# dashboard.net
KiCad netlist of a schematic drawn in EAGLE
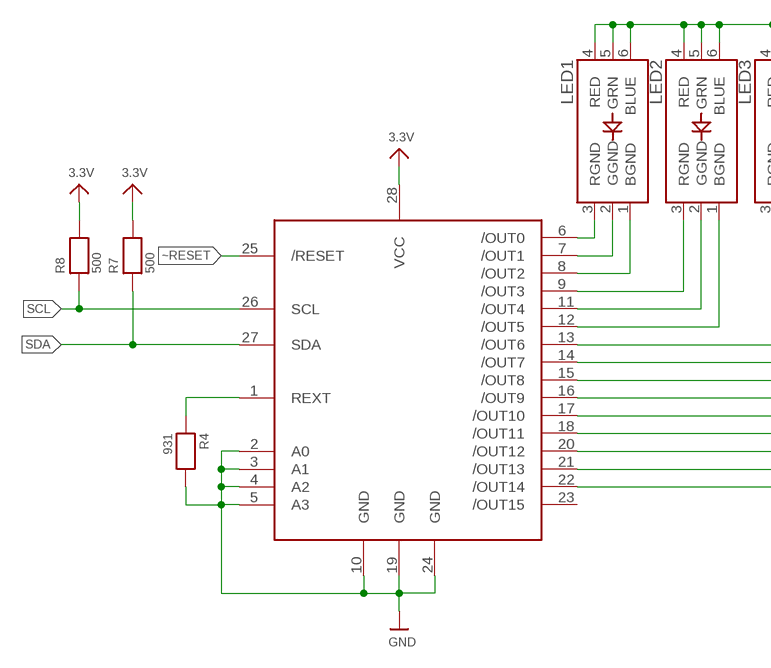
[diagram p0: schematic, sheet 1, part 1 of 2]
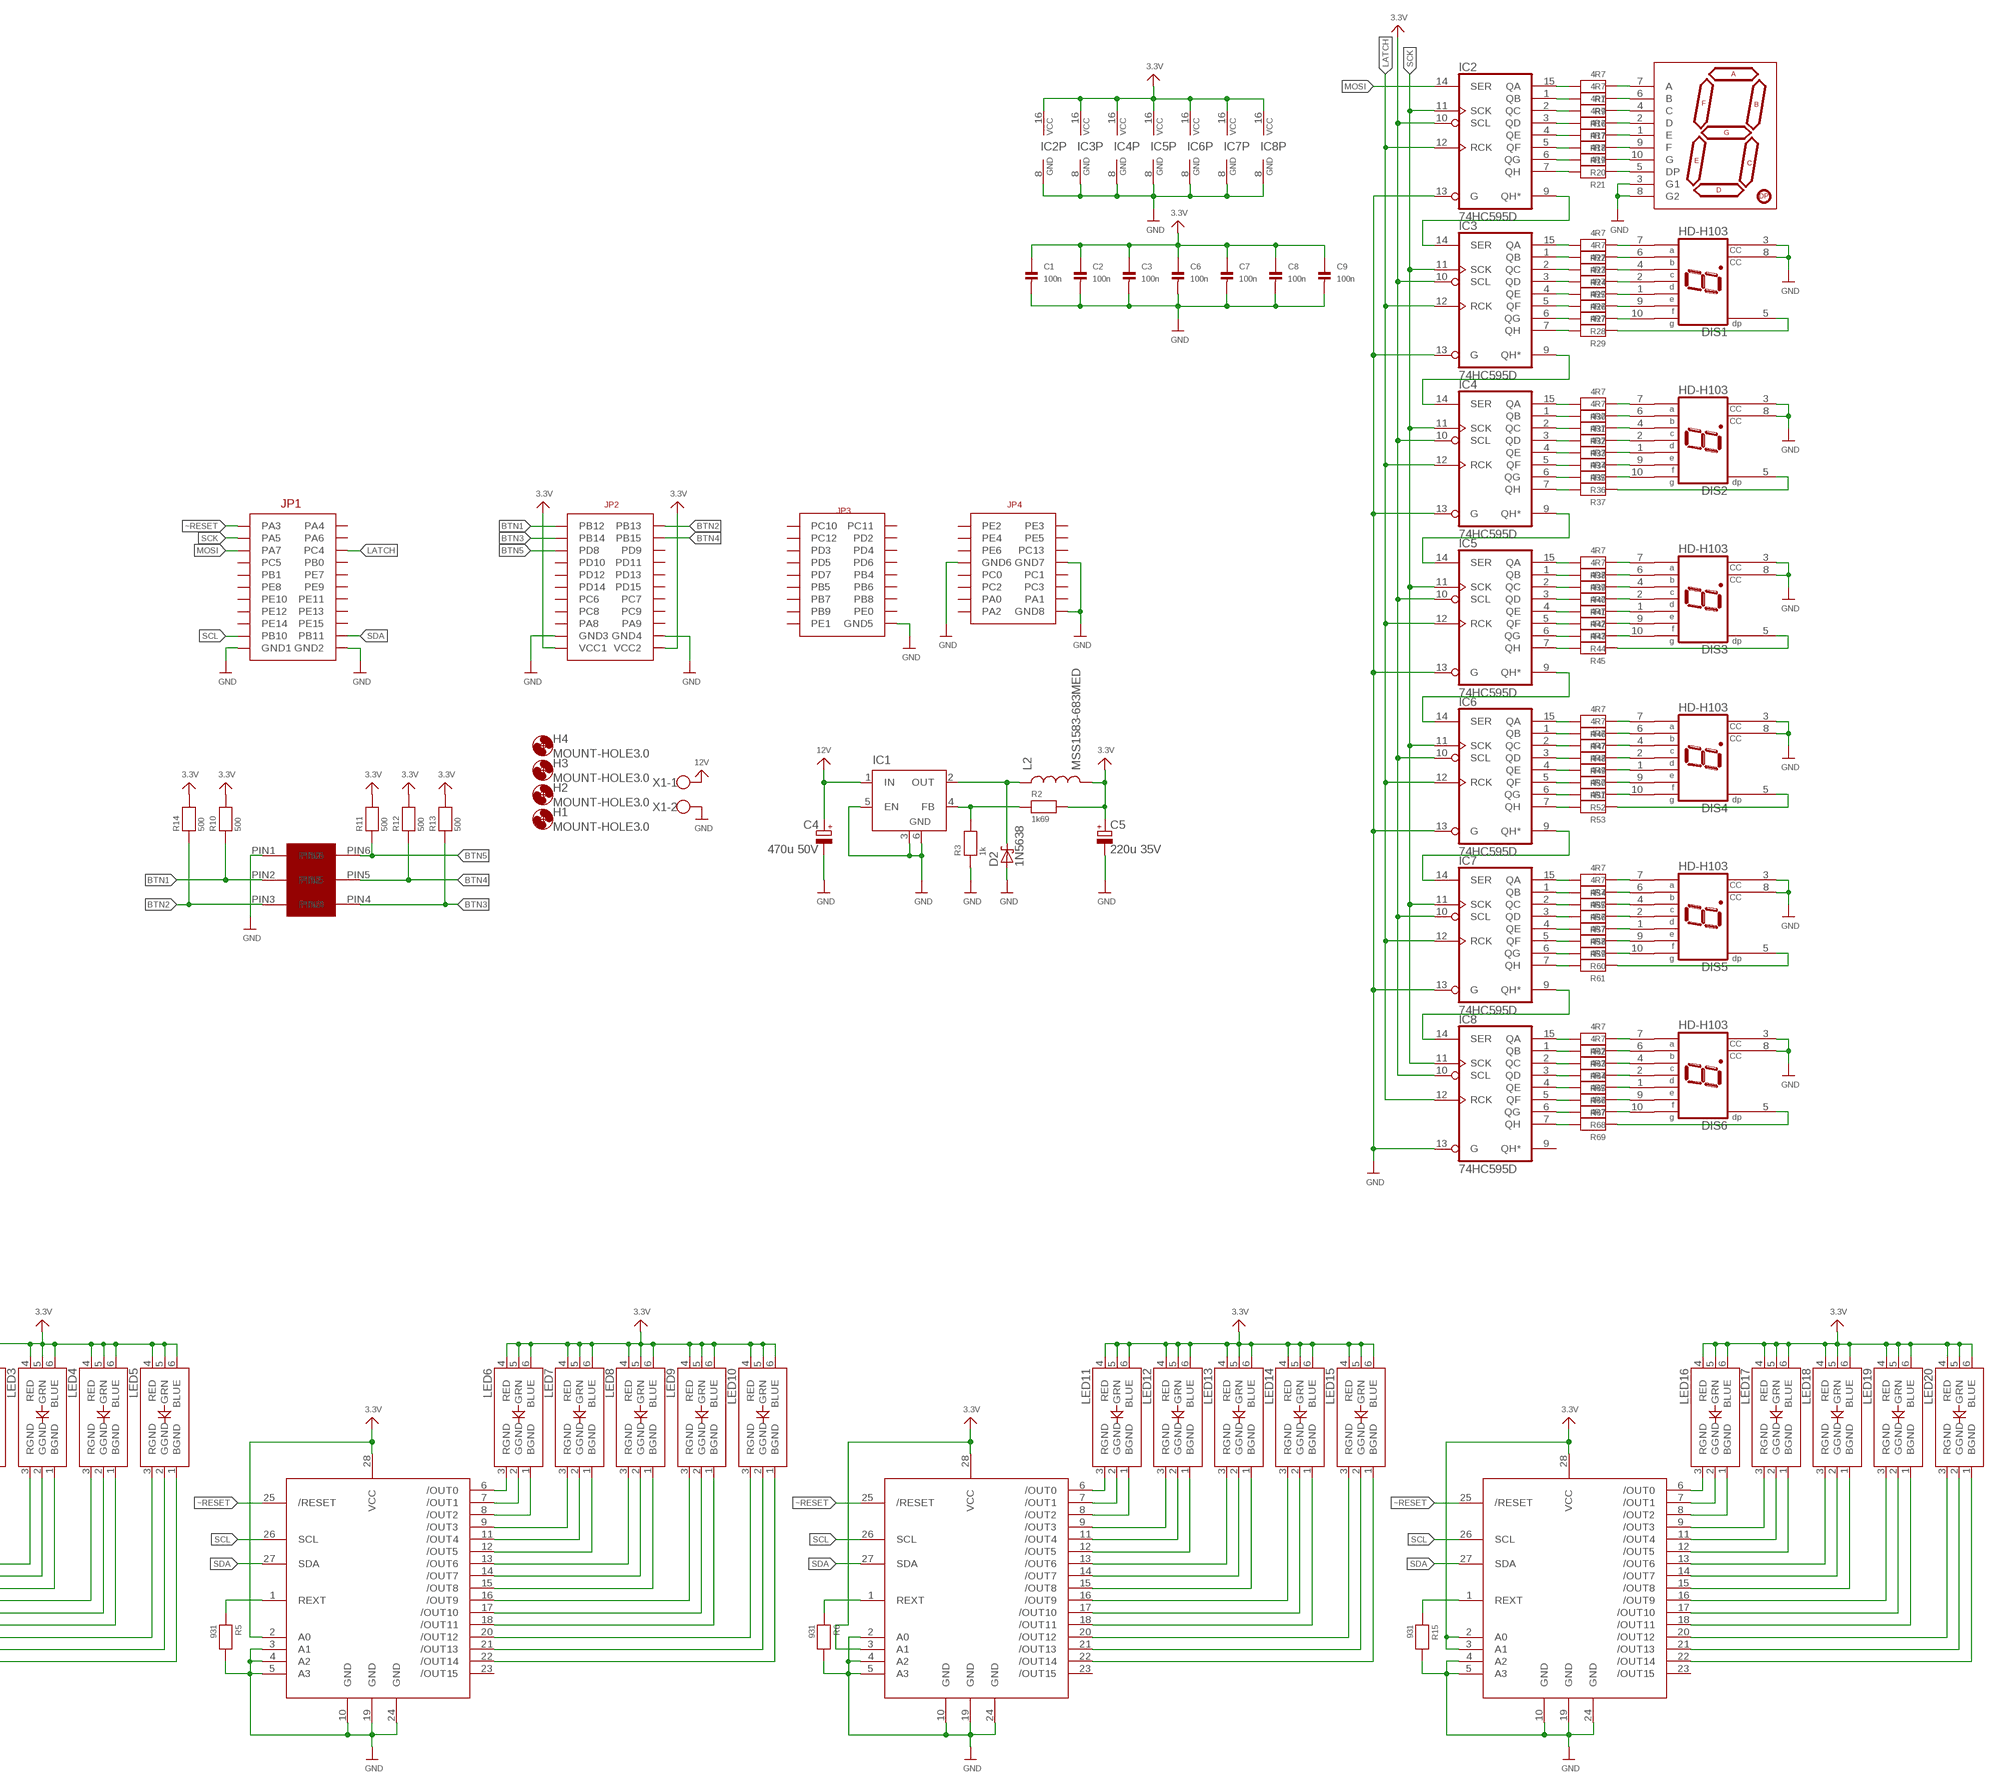
[diagram p1: schematic, sheet 1, part 2 of 2]

(export (version "E")
  (design (tool "Eeschema 10.0.6"))
  (components
    (comp (ref "C1")
      (value "100n")
      (footprint "eagle-import:_0603")
      (libsource (lib "eagle-import") (part "CAP_CERAMIC_0603"))
    )
    (comp (ref "C2")
      (value "100n")
      (footprint "eagle-import:_0603")
      (libsource (lib "eagle-import") (part "CAP_CERAMIC_0603"))
    )
    (comp (ref "C3")
      (value "100n")
      (footprint "eagle-import:_0603")
      (libsource (lib "eagle-import") (part "CAP_CERAMIC_0603"))
    )
    (comp (ref "C4")
      (value "470u 50V")
      (footprint "eagle-import:E5-13")
      (libsource (lib "eagle-import") (part "CPOL-EUE5-13"))
    )
    (comp (ref "C5")
      (value "220u 35V")
      (footprint "eagle-import:E3,5-8")
      (libsource (lib "eagle-import") (part "CPOL-EUE3.5-8"))
    )
    (comp (ref "C6")
      (value "100n")
      (footprint "eagle-import:_0603")
      (libsource (lib "eagle-import") (part "CAP_CERAMIC_0603"))
    )
    (comp (ref "C7")
      (value "100n")
      (footprint "eagle-import:_0603")
      (libsource (lib "eagle-import") (part "CAP_CERAMIC_0603"))
    )
    (comp (ref "C8")
      (value "100n")
      (footprint "eagle-import:_0603")
      (libsource (lib "eagle-import") (part "CAP_CERAMIC_0603"))
    )
    (comp (ref "C9")
      (value "100n")
      (footprint "eagle-import:_0603")
      (libsource (lib "eagle-import") (part "CAP_CERAMIC_0603"))
    )
    (comp (ref "D2")
      (value "1N5638")
      (footprint "eagle-import:DO13M")
      (libsource (lib "eagle-import") (part "1N5638"))
    )
    (comp (ref "DIS1")
      (value "HD-H103")
      (footprint "eagle-import:HDSP-M")
      (libsource (lib "eagle-import") (part "HD-H103"))
    )
    (comp (ref "DIS2")
      (value "HD-H103")
      (footprint "eagle-import:HDSP-M")
      (libsource (lib "eagle-import") (part "HD-H103"))
    )
    (comp (ref "DIS3")
      (value "HD-H103")
      (footprint "eagle-import:HDSP-M")
      (libsource (lib "eagle-import") (part "HD-H103"))
    )
    (comp (ref "DIS4")
      (value "HD-H103")
      (footprint "eagle-import:HDSP-M")
      (libsource (lib "eagle-import") (part "HD-H103"))
    )
    (comp (ref "DIS5")
      (value "HD-H103")
      (footprint "eagle-import:HDSP-M")
      (libsource (lib "eagle-import") (part "HD-H103"))
    )
    (comp (ref "DIS6")
      (value "HD-H103")
      (footprint "eagle-import:HDSP-M")
      (libsource (lib "eagle-import") (part "HD-H103"))
    )
    (comp (ref "H1")
      (value "MOUNT-HOLE3.0")
      (footprint "eagle-import:3,0")
      (libsource (lib "eagle-import") (part "MOUNT-HOLE3.0"))
    )
    (comp (ref "H2")
      (value "MOUNT-HOLE3.0")
      (footprint "eagle-import:3,0")
      (libsource (lib "eagle-import") (part "MOUNT-HOLE3.0"))
    )
    (comp (ref "H3")
      (value "MOUNT-HOLE3.0")
      (footprint "eagle-import:3,0")
      (libsource (lib "eagle-import") (part "MOUNT-HOLE3.0"))
    )
    (comp (ref "H4")
      (value "MOUNT-HOLE3.0")
      (footprint "eagle-import:3,0")
      (libsource (lib "eagle-import") (part "MOUNT-HOLE3.0"))
    )
    (comp (ref "IC1")
      (value "LM2596S")
      (footprint "eagle-import:TO263-5")
      (libsource (lib "eagle-import") (part "LM2596S"))
    )
    (comp (ref "IC2")
      (value "74HC595D")
      (footprint "eagle-import:SO16")
      (libsource (lib "eagle-import") (part "74595DHC"))
    )
    (comp (ref "IC3")
      (value "74HC595D")
      (footprint "eagle-import:SO16")
      (libsource (lib "eagle-import") (part "74595DHC"))
    )
    (comp (ref "IC4")
      (value "74HC595D")
      (footprint "eagle-import:SO16")
      (libsource (lib "eagle-import") (part "74595DHC"))
    )
    (comp (ref "IC5")
      (value "74HC595D")
      (footprint "eagle-import:SO16")
      (libsource (lib "eagle-import") (part "74595DHC"))
    )
    (comp (ref "IC6")
      (value "74HC595D")
      (footprint "eagle-import:SO16")
      (libsource (lib "eagle-import") (part "74595DHC"))
    )
    (comp (ref "IC7")
      (value "74HC595D")
      (footprint "eagle-import:SO16")
      (libsource (lib "eagle-import") (part "74595DHC"))
    )
    (comp (ref "IC8")
      (value "74HC595D")
      (footprint "eagle-import:SO16")
      (libsource (lib "eagle-import") (part "74595DHC"))
    )
    (comp (ref "L2")
      (value "MSS1583-683MED")
      (footprint "eagle-import:CDRH125")
      (libsource (lib "eagle-import") (part "INDUCTORPWR"))
    )
    (comp (ref "LED1")
      (value "LED_RGB_PLCC6CREE-CLV6A")
      (footprint "eagle-import:RGBLED_PLCC6")
      (libsource (lib "eagle-import") (part "LED_RGB_PLCC6CREE-CLV6A"))
    )
    (comp (ref "LED2")
      (value "LED_RGB_PLCC6CREE-CLV6A")
      (footprint "eagle-import:RGBLED_PLCC6")
      (libsource (lib "eagle-import") (part "LED_RGB_PLCC6CREE-CLV6A"))
    )
    (comp (ref "LED3")
      (value "LED_RGB_PLCC6CREE-CLV6A")
      (footprint "eagle-import:RGBLED_PLCC6")
      (libsource (lib "eagle-import") (part "LED_RGB_PLCC6CREE-CLV6A"))
    )
    (comp (ref "LED4")
      (value "LED_RGB_PLCC6CREE-CLV6A")
      (footprint "eagle-import:RGBLED_PLCC6")
      (libsource (lib "eagle-import") (part "LED_RGB_PLCC6CREE-CLV6A"))
    )
    (comp (ref "LED5")
      (value "LED_RGB_PLCC6CREE-CLV6A")
      (footprint "eagle-import:RGBLED_PLCC6")
      (libsource (lib "eagle-import") (part "LED_RGB_PLCC6CREE-CLV6A"))
    )
    (comp (ref "LED6")
      (value "LED_RGB_PLCC6CREE-CLV6A")
      (footprint "eagle-import:RGBLED_PLCC6")
      (libsource (lib "eagle-import") (part "LED_RGB_PLCC6CREE-CLV6A"))
    )
    (comp (ref "LED7")
      (value "LED_RGB_PLCC6CREE-CLV6A")
      (footprint "eagle-import:RGBLED_PLCC6")
      (libsource (lib "eagle-import") (part "LED_RGB_PLCC6CREE-CLV6A"))
    )
    (comp (ref "LED8")
      (value "LED_RGB_PLCC6CREE-CLV6A")
      (footprint "eagle-import:RGBLED_PLCC6")
      (libsource (lib "eagle-import") (part "LED_RGB_PLCC6CREE-CLV6A"))
    )
    (comp (ref "LED9")
      (value "LED_RGB_PLCC6CREE-CLV6A")
      (footprint "eagle-import:RGBLED_PLCC6")
      (libsource (lib "eagle-import") (part "LED_RGB_PLCC6CREE-CLV6A"))
    )
    (comp (ref "LED10")
      (value "LED_RGB_PLCC6CREE-CLV6A")
      (footprint "eagle-import:RGBLED_PLCC6")
      (libsource (lib "eagle-import") (part "LED_RGB_PLCC6CREE-CLV6A"))
    )
    (comp (ref "LED11")
      (value "LED_RGB_PLCC6CREE-CLV6A")
      (footprint "eagle-import:RGBLED_PLCC6")
      (libsource (lib "eagle-import") (part "LED_RGB_PLCC6CREE-CLV6A"))
    )
    (comp (ref "LED12")
      (value "LED_RGB_PLCC6CREE-CLV6A")
      (footprint "eagle-import:RGBLED_PLCC6")
      (libsource (lib "eagle-import") (part "LED_RGB_PLCC6CREE-CLV6A"))
    )
    (comp (ref "LED13")
      (value "LED_RGB_PLCC6CREE-CLV6A")
      (footprint "eagle-import:RGBLED_PLCC6")
      (libsource (lib "eagle-import") (part "LED_RGB_PLCC6CREE-CLV6A"))
    )
    (comp (ref "LED14")
      (value "LED_RGB_PLCC6CREE-CLV6A")
      (footprint "eagle-import:RGBLED_PLCC6")
      (libsource (lib "eagle-import") (part "LED_RGB_PLCC6CREE-CLV6A"))
    )
    (comp (ref "LED15")
      (value "LED_RGB_PLCC6CREE-CLV6A")
      (footprint "eagle-import:RGBLED_PLCC6")
      (libsource (lib "eagle-import") (part "LED_RGB_PLCC6CREE-CLV6A"))
    )
    (comp (ref "LED16")
      (value "LED_RGB_PLCC6CREE-CLV6A")
      (footprint "eagle-import:RGBLED_PLCC6")
      (libsource (lib "eagle-import") (part "LED_RGB_PLCC6CREE-CLV6A"))
    )
    (comp (ref "LED17")
      (value "LED_RGB_PLCC6CREE-CLV6A")
      (footprint "eagle-import:RGBLED_PLCC6")
      (libsource (lib "eagle-import") (part "LED_RGB_PLCC6CREE-CLV6A"))
    )
    (comp (ref "LED18")
      (value "LED_RGB_PLCC6CREE-CLV6A")
      (footprint "eagle-import:RGBLED_PLCC6")
      (libsource (lib "eagle-import") (part "LED_RGB_PLCC6CREE-CLV6A"))
    )
    (comp (ref "LED19")
      (value "LED_RGB_PLCC6CREE-CLV6A")
      (footprint "eagle-import:RGBLED_PLCC6")
      (libsource (lib "eagle-import") (part "LED_RGB_PLCC6CREE-CLV6A"))
    )
    (comp (ref "LED20")
      (value "LED_RGB_PLCC6CREE-CLV6A")
      (footprint "eagle-import:RGBLED_PLCC6")
      (libsource (lib "eagle-import") (part "LED_RGB_PLCC6CREE-CLV6A"))
    )
    (comp (ref "R1")
      (value "4R7")
      (footprint "eagle-import:_0603")
      (libsource (lib "eagle-import") (part "RESISTOR_0603"))
    )
    (comp (ref "R2")
      (value "1k69")
      (footprint "eagle-import:_0603")
      (libsource (lib "eagle-import") (part "RESISTOR_0603"))
    )
    (comp (ref "R3")
      (value "1k")
      (footprint "eagle-import:_0603")
      (libsource (lib "eagle-import") (part "RESISTOR_0603"))
    )
    (comp (ref "R4")
      (value "931")
      (footprint "eagle-import:_0603")
      (libsource (lib "eagle-import") (part "RESISTOR_0603"))
    )
    (comp (ref "R5")
      (value "931")
      (footprint "eagle-import:_0603")
      (libsource (lib "eagle-import") (part "RESISTOR_0603"))
    )
    (comp (ref "R6")
      (value "931")
      (footprint "eagle-import:_0603")
      (libsource (lib "eagle-import") (part "RESISTOR_0603"))
    )
    (comp (ref "R7")
      (value "500")
      (footprint "eagle-import:_0603")
      (libsource (lib "eagle-import") (part "RESISTOR_0603"))
    )
    (comp (ref "R8")
      (value "500")
      (footprint "eagle-import:_0603")
      (libsource (lib "eagle-import") (part "RESISTOR_0603"))
    )
    (comp (ref "R9")
      (value "4R7")
      (footprint "eagle-import:_0603")
      (libsource (lib "eagle-import") (part "RESISTOR_0603"))
    )
    (comp (ref "R10")
      (value "500")
      (footprint "eagle-import:_0805")
      (libsource (lib "eagle-import") (part "RESISTOR_0805"))
    )
    (comp (ref "R11")
      (value "500")
      (footprint "eagle-import:_0805")
      (libsource (lib "eagle-import") (part "RESISTOR_0805"))
    )
    (comp (ref "R12")
      (value "500")
      (footprint "eagle-import:_0805")
      (libsource (lib "eagle-import") (part "RESISTOR_0805"))
    )
    (comp (ref "R13")
      (value "500")
      (footprint "eagle-import:_0805")
      (libsource (lib "eagle-import") (part "RESISTOR_0805"))
    )
    (comp (ref "R14")
      (value "500")
      (footprint "eagle-import:_0805")
      (libsource (lib "eagle-import") (part "RESISTOR_0805"))
    )
    (comp (ref "R15")
      (value "931")
      (footprint "eagle-import:_0603")
      (libsource (lib "eagle-import") (part "RESISTOR_0603"))
    )
    (comp (ref "R16")
      (value "4R7")
      (footprint "eagle-import:_0603")
      (libsource (lib "eagle-import") (part "RESISTOR_0603"))
    )
    (comp (ref "R17")
      (value "4R7")
      (footprint "eagle-import:_0603")
      (libsource (lib "eagle-import") (part "RESISTOR_0603"))
    )
    (comp (ref "R18")
      (value "4R7")
      (footprint "eagle-import:_0603")
      (libsource (lib "eagle-import") (part "RESISTOR_0603"))
    )
    (comp (ref "R19")
      (value "4R7")
      (footprint "eagle-import:_0603")
      (libsource (lib "eagle-import") (part "RESISTOR_0603"))
    )
    (comp (ref "R20")
      (value "4R7")
      (footprint "eagle-import:_0603")
      (libsource (lib "eagle-import") (part "RESISTOR_0603"))
    )
    (comp (ref "R21")
      (value "4R7")
      (footprint "eagle-import:_0603")
      (libsource (lib "eagle-import") (part "RESISTOR_0603"))
    )
    (comp (ref "R22")
      (value "4R7")
      (footprint "eagle-import:_0603")
      (libsource (lib "eagle-import") (part "RESISTOR_0603"))
    )
    (comp (ref "R23")
      (value "4R7")
      (footprint "eagle-import:_0603")
      (libsource (lib "eagle-import") (part "RESISTOR_0603"))
    )
    (comp (ref "R24")
      (value "4R7")
      (footprint "eagle-import:_0603")
      (libsource (lib "eagle-import") (part "RESISTOR_0603"))
    )
    (comp (ref "R25")
      (value "4R7")
      (footprint "eagle-import:_0603")
      (libsource (lib "eagle-import") (part "RESISTOR_0603"))
    )
    (comp (ref "R26")
      (value "4R7")
      (footprint "eagle-import:_0603")
      (libsource (lib "eagle-import") (part "RESISTOR_0603"))
    )
    (comp (ref "R27")
      (value "4R7")
      (footprint "eagle-import:_0603")
      (libsource (lib "eagle-import") (part "RESISTOR_0603"))
    )
    (comp (ref "R28")
      (value "4R7")
      (footprint "eagle-import:_0603")
      (libsource (lib "eagle-import") (part "RESISTOR_0603"))
    )
    (comp (ref "R29")
      (value "4R7")
      (footprint "eagle-import:_0603")
      (libsource (lib "eagle-import") (part "RESISTOR_0603"))
    )
    (comp (ref "R30")
      (value "4R7")
      (footprint "eagle-import:_0603")
      (libsource (lib "eagle-import") (part "RESISTOR_0603"))
    )
    (comp (ref "R31")
      (value "4R7")
      (footprint "eagle-import:_0603")
      (libsource (lib "eagle-import") (part "RESISTOR_0603"))
    )
    (comp (ref "R32")
      (value "4R7")
      (footprint "eagle-import:_0603")
      (libsource (lib "eagle-import") (part "RESISTOR_0603"))
    )
    (comp (ref "R33")
      (value "4R7")
      (footprint "eagle-import:_0603")
      (libsource (lib "eagle-import") (part "RESISTOR_0603"))
    )
    (comp (ref "R34")
      (value "4R7")
      (footprint "eagle-import:_0603")
      (libsource (lib "eagle-import") (part "RESISTOR_0603"))
    )
    (comp (ref "R35")
      (value "4R7")
      (footprint "eagle-import:_0603")
      (libsource (lib "eagle-import") (part "RESISTOR_0603"))
    )
    (comp (ref "R36")
      (value "4R7")
      (footprint "eagle-import:_0603")
      (libsource (lib "eagle-import") (part "RESISTOR_0603"))
    )
    (comp (ref "R37")
      (value "4R7")
      (footprint "eagle-import:_0603")
      (libsource (lib "eagle-import") (part "RESISTOR_0603"))
    )
    (comp (ref "R38")
      (value "4R7")
      (footprint "eagle-import:_0603")
      (libsource (lib "eagle-import") (part "RESISTOR_0603"))
    )
    (comp (ref "R39")
      (value "4R7")
      (footprint "eagle-import:_0603")
      (libsource (lib "eagle-import") (part "RESISTOR_0603"))
    )
    (comp (ref "R40")
      (value "4R7")
      (footprint "eagle-import:_0603")
      (libsource (lib "eagle-import") (part "RESISTOR_0603"))
    )
    (comp (ref "R41")
      (value "4R7")
      (footprint "eagle-import:_0603")
      (libsource (lib "eagle-import") (part "RESISTOR_0603"))
    )
    (comp (ref "R42")
      (value "4R7")
      (footprint "eagle-import:_0603")
      (libsource (lib "eagle-import") (part "RESISTOR_0603"))
    )
    (comp (ref "R43")
      (value "4R7")
      (footprint "eagle-import:_0603")
      (libsource (lib "eagle-import") (part "RESISTOR_0603"))
    )
    (comp (ref "R44")
      (value "4R7")
      (footprint "eagle-import:_0603")
      (libsource (lib "eagle-import") (part "RESISTOR_0603"))
    )
    (comp (ref "R45")
      (value "4R7")
      (footprint "eagle-import:_0603")
      (libsource (lib "eagle-import") (part "RESISTOR_0603"))
    )
    (comp (ref "R46")
      (value "4R7")
      (footprint "eagle-import:_0603")
      (libsource (lib "eagle-import") (part "RESISTOR_0603"))
    )
    (comp (ref "R47")
      (value "4R7")
      (footprint "eagle-import:_0603")
      (libsource (lib "eagle-import") (part "RESISTOR_0603"))
    )
    (comp (ref "R48")
      (value "4R7")
      (footprint "eagle-import:_0603")
      (libsource (lib "eagle-import") (part "RESISTOR_0603"))
    )
    (comp (ref "R49")
      (value "4R7")
      (footprint "eagle-import:_0603")
      (libsource (lib "eagle-import") (part "RESISTOR_0603"))
    )
    (comp (ref "R50")
      (value "4R7")
      (footprint "eagle-import:_0603")
      (libsource (lib "eagle-import") (part "RESISTOR_0603"))
    )
    (comp (ref "R51")
      (value "4R7")
      (footprint "eagle-import:_0603")
      (libsource (lib "eagle-import") (part "RESISTOR_0603"))
    )
    (comp (ref "R52")
      (value "4R7")
      (footprint "eagle-import:_0603")
      (libsource (lib "eagle-import") (part "RESISTOR_0603"))
    )
    (comp (ref "R53")
      (value "4R7")
      (footprint "eagle-import:_0603")
      (libsource (lib "eagle-import") (part "RESISTOR_0603"))
    )
    (comp (ref "R54")
      (value "4R7")
      (footprint "eagle-import:_0603")
      (libsource (lib "eagle-import") (part "RESISTOR_0603"))
    )
    (comp (ref "R55")
      (value "4R7")
      (footprint "eagle-import:_0603")
      (libsource (lib "eagle-import") (part "RESISTOR_0603"))
    )
    (comp (ref "R56")
      (value "4R7")
      (footprint "eagle-import:_0603")
      (libsource (lib "eagle-import") (part "RESISTOR_0603"))
    )
    (comp (ref "R57")
      (value "4R7")
      (footprint "eagle-import:_0603")
      (libsource (lib "eagle-import") (part "RESISTOR_0603"))
    )
    (comp (ref "R58")
      (value "4R7")
      (footprint "eagle-import:_0603")
      (libsource (lib "eagle-import") (part "RESISTOR_0603"))
    )
    (comp (ref "R59")
      (value "4R7")
      (footprint "eagle-import:_0603")
      (libsource (lib "eagle-import") (part "RESISTOR_0603"))
    )
    (comp (ref "R60")
      (value "4R7")
      (footprint "eagle-import:_0603")
      (libsource (lib "eagle-import") (part "RESISTOR_0603"))
    )
    (comp (ref "R61")
      (value "4R7")
      (footprint "eagle-import:_0603")
      (libsource (lib "eagle-import") (part "RESISTOR_0603"))
    )
    (comp (ref "R62")
      (value "4R7")
      (footprint "eagle-import:_0603")
      (libsource (lib "eagle-import") (part "RESISTOR_0603"))
    )
    (comp (ref "R63")
      (value "4R7")
      (footprint "eagle-import:_0603")
      (libsource (lib "eagle-import") (part "RESISTOR_0603"))
    )
    (comp (ref "R64")
      (value "4R7")
      (footprint "eagle-import:_0603")
      (libsource (lib "eagle-import") (part "RESISTOR_0603"))
    )
    (comp (ref "R65")
      (value "4R7")
      (footprint "eagle-import:_0603")
      (libsource (lib "eagle-import") (part "RESISTOR_0603"))
    )
    (comp (ref "R66")
      (value "4R7")
      (footprint "eagle-import:_0603")
      (libsource (lib "eagle-import") (part "RESISTOR_0603"))
    )
    (comp (ref "R67")
      (value "4R7")
      (footprint "eagle-import:_0603")
      (libsource (lib "eagle-import") (part "RESISTOR_0603"))
    )
    (comp (ref "R68")
      (value "4R7")
      (footprint "eagle-import:_0603")
      (libsource (lib "eagle-import") (part "RESISTOR_0603"))
    )
    (comp (ref "R69")
      (value "4R7")
      (footprint "eagle-import:_0603")
      (libsource (lib "eagle-import") (part "RESISTOR_0603"))
    )
    (comp (ref "U$1")
      (value "CPU-BOARD")
      (footprint "eagle-import:CPU-BOARD-JP1")
      (libsource (lib "eagle-import") (part "CPU-BOARD"))
    )
    (comp (ref "U$9")
      (value "7-SEGMENT-DISPLAY-1\"-RED")
      (footprint "eagle-import:7-SEGMENT-1_PTH")
      (libsource (lib "eagle-import") (part "7-SEGMENT-DISPLAY-1{dblquote}-RED"))
    )
    (comp (ref "U$30")
      (value "TLC59116")
      (footprint "eagle-import:TSSOP28")
      (libsource (lib "eagle-import") (part "TLC59116"))
    )
    (comp (ref "U$33")
      (value "TLC59116")
      (footprint "eagle-import:TSSOP28")
      (libsource (lib "eagle-import") (part "TLC59116"))
    )
    (comp (ref "U$36")
      (value "TLC59116")
      (footprint "eagle-import:TSSOP28")
      (libsource (lib "eagle-import") (part "TLC59116"))
    )
    (comp (ref "U$42")
      (value "MICROFIT6")
      (footprint "eagle-import:MICROFIT6SOCK")
      (libsource (lib "eagle-import") (part "MICROFIT6"))
    )
    (comp (ref "U$51")
      (value "TLC59116")
      (footprint "eagle-import:TSSOP28")
      (libsource (lib "eagle-import") (part "TLC59116"))
    )
    (comp (ref "X1")
      (value "W237-102")
      (footprint "eagle-import:W237-102")
      (fields (field (name "MPN") "237-102"))
      (libsource (lib "eagle-import") (part "W237-102"))
    )
  )
  (nets
    (net (code "1") (name "/~{RESET}") (class "Default")
      (node (ref "U$1") (pin "P$1") (pinfunction "PA3_P$1") (pintype "bidirectional"))
      (node (ref "U$30") (pin "25") (pinfunction "/RESET_25") (pintype "bidirectional"))
      (node (ref "U$33") (pin "25") (pinfunction "/RESET_25") (pintype "bidirectional"))
      (node (ref "U$36") (pin "25") (pinfunction "/RESET_25") (pintype "bidirectional"))
      (node (ref "U$51") (pin "25") (pinfunction "/RESET_25") (pintype "bidirectional"))
    )
    (net (code "2") (name "3.3V") (class "Default")
      (node (ref "C1") (pin "1") (pinfunction "P$1_1") (pintype "passive"))
      (node (ref "C2") (pin "1") (pinfunction "P$1_1") (pintype "passive"))
      (node (ref "C3") (pin "1") (pinfunction "P$1_1") (pintype "passive"))
      (node (ref "C5") (pin "+") (pinfunction "+_+") (pintype "passive"))
      (node (ref "C6") (pin "1") (pinfunction "P$1_1") (pintype "passive"))
      (node (ref "C7") (pin "1") (pinfunction "P$1_1") (pintype "passive"))
      (node (ref "C8") (pin "1") (pinfunction "P$1_1") (pintype "passive"))
      (node (ref "C9") (pin "1") (pinfunction "P$1_1") (pintype "passive"))
      (node (ref "IC2") (pin "10") (pinfunction "SCL_10") (pintype "input"))
      (node (ref "IC2") (pin "16") (pinfunction "VCC_16") (pintype "power_in"))
      (node (ref "IC3") (pin "10") (pinfunction "SCL_10") (pintype "input"))
      (node (ref "IC3") (pin "16") (pinfunction "VCC_16") (pintype "power_in"))
      (node (ref "IC4") (pin "10") (pinfunction "SCL_10") (pintype "input"))
      (node (ref "IC4") (pin "16") (pinfunction "VCC_16") (pintype "power_in"))
      (node (ref "IC5") (pin "10") (pinfunction "SCL_10") (pintype "input"))
      (node (ref "IC5") (pin "16") (pinfunction "VCC_16") (pintype "power_in"))
      (node (ref "IC6") (pin "10") (pinfunction "SCL_10") (pintype "input"))
      (node (ref "IC6") (pin "16") (pinfunction "VCC_16") (pintype "power_in"))
      (node (ref "IC7") (pin "10") (pinfunction "SCL_10") (pintype "input"))
      (node (ref "IC7") (pin "16") (pinfunction "VCC_16") (pintype "power_in"))
      (node (ref "IC8") (pin "10") (pinfunction "SCL_10") (pintype "input"))
      (node (ref "IC8") (pin "16") (pinfunction "VCC_16") (pintype "power_in"))
      (node (ref "L2") (pin "2") (pinfunction "2_2") (pintype "passive"))
      (node (ref "LED1") (pin "4") (pinfunction "RED_4") (pintype "bidirectional"))
      (node (ref "LED1") (pin "5") (pinfunction "GRN_5") (pintype "bidirectional"))
      (node (ref "LED1") (pin "6") (pinfunction "BLUE_6") (pintype "bidirectional"))
      (node (ref "LED10") (pin "4") (pinfunction "RED_4") (pintype "bidirectional"))
      (node (ref "LED10") (pin "5") (pinfunction "GRN_5") (pintype "bidirectional"))
      (node (ref "LED10") (pin "6") (pinfunction "BLUE_6") (pintype "bidirectional"))
      (node (ref "LED11") (pin "4") (pinfunction "RED_4") (pintype "bidirectional"))
      (node (ref "LED11") (pin "5") (pinfunction "GRN_5") (pintype "bidirectional"))
      (node (ref "LED11") (pin "6") (pinfunction "BLUE_6") (pintype "bidirectional"))
      (node (ref "LED12") (pin "4") (pinfunction "RED_4") (pintype "bidirectional"))
      (node (ref "LED12") (pin "5") (pinfunction "GRN_5") (pintype "bidirectional"))
      (node (ref "LED12") (pin "6") (pinfunction "BLUE_6") (pintype "bidirectional"))
      (node (ref "LED13") (pin "4") (pinfunction "RED_4") (pintype "bidirectional"))
      (node (ref "LED13") (pin "5") (pinfunction "GRN_5") (pintype "bidirectional"))
      (node (ref "LED13") (pin "6") (pinfunction "BLUE_6") (pintype "bidirectional"))
      (node (ref "LED14") (pin "4") (pinfunction "RED_4") (pintype "bidirectional"))
      (node (ref "LED14") (pin "5") (pinfunction "GRN_5") (pintype "bidirectional"))
      (node (ref "LED14") (pin "6") (pinfunction "BLUE_6") (pintype "bidirectional"))
      (node (ref "LED15") (pin "4") (pinfunction "RED_4") (pintype "bidirectional"))
      (node (ref "LED15") (pin "5") (pinfunction "GRN_5") (pintype "bidirectional"))
      (node (ref "LED15") (pin "6") (pinfunction "BLUE_6") (pintype "bidirectional"))
      (node (ref "LED16") (pin "4") (pinfunction "RED_4") (pintype "bidirectional"))
      (node (ref "LED16") (pin "5") (pinfunction "GRN_5") (pintype "bidirectional"))
      (node (ref "LED16") (pin "6") (pinfunction "BLUE_6") (pintype "bidirectional"))
      (node (ref "LED17") (pin "4") (pinfunction "RED_4") (pintype "bidirectional"))
      (node (ref "LED17") (pin "5") (pinfunction "GRN_5") (pintype "bidirectional"))
      (node (ref "LED17") (pin "6") (pinfunction "BLUE_6") (pintype "bidirectional"))
      (node (ref "LED18") (pin "4") (pinfunction "RED_4") (pintype "bidirectional"))
      (node (ref "LED18") (pin "5") (pinfunction "GRN_5") (pintype "bidirectional"))
      (node (ref "LED18") (pin "6") (pinfunction "BLUE_6") (pintype "bidirectional"))
      (node (ref "LED19") (pin "4") (pinfunction "RED_4") (pintype "bidirectional"))
      (node (ref "LED19") (pin "5") (pinfunction "GRN_5") (pintype "bidirectional"))
      (node (ref "LED19") (pin "6") (pinfunction "BLUE_6") (pintype "bidirectional"))
      (node (ref "LED2") (pin "4") (pinfunction "RED_4") (pintype "bidirectional"))
      (node (ref "LED2") (pin "5") (pinfunction "GRN_5") (pintype "bidirectional"))
      (node (ref "LED2") (pin "6") (pinfunction "BLUE_6") (pintype "bidirectional"))
      (node (ref "LED20") (pin "4") (pinfunction "RED_4") (pintype "bidirectional"))
      (node (ref "LED20") (pin "5") (pinfunction "GRN_5") (pintype "bidirectional"))
      (node (ref "LED20") (pin "6") (pinfunction "BLUE_6") (pintype "bidirectional"))
      (node (ref "LED3") (pin "4") (pinfunction "RED_4") (pintype "bidirectional"))
      (node (ref "LED3") (pin "5") (pinfunction "GRN_5") (pintype "bidirectional"))
      (node (ref "LED3") (pin "6") (pinfunction "BLUE_6") (pintype "bidirectional"))
      (node (ref "LED4") (pin "4") (pinfunction "RED_4") (pintype "bidirectional"))
      (node (ref "LED4") (pin "5") (pinfunction "GRN_5") (pintype "bidirectional"))
      (node (ref "LED4") (pin "6") (pinfunction "BLUE_6") (pintype "bidirectional"))
      (node (ref "LED5") (pin "4") (pinfunction "RED_4") (pintype "bidirectional"))
      (node (ref "LED5") (pin "5") (pinfunction "GRN_5") (pintype "bidirectional"))
      (node (ref "LED5") (pin "6") (pinfunction "BLUE_6") (pintype "bidirectional"))
      (node (ref "LED6") (pin "4") (pinfunction "RED_4") (pintype "bidirectional"))
      (node (ref "LED6") (pin "5") (pinfunction "GRN_5") (pintype "bidirectional"))
      (node (ref "LED6") (pin "6") (pinfunction "BLUE_6") (pintype "bidirectional"))
      (node (ref "LED7") (pin "4") (pinfunction "RED_4") (pintype "bidirectional"))
      (node (ref "LED7") (pin "5") (pinfunction "GRN_5") (pintype "bidirectional"))
      (node (ref "LED7") (pin "6") (pinfunction "BLUE_6") (pintype "bidirectional"))
      (node (ref "LED8") (pin "4") (pinfunction "RED_4") (pintype "bidirectional"))
      (node (ref "LED8") (pin "5") (pinfunction "GRN_5") (pintype "bidirectional"))
      (node (ref "LED8") (pin "6") (pinfunction "BLUE_6") (pintype "bidirectional"))
      (node (ref "LED9") (pin "4") (pinfunction "RED_4") (pintype "bidirectional"))
      (node (ref "LED9") (pin "5") (pinfunction "GRN_5") (pintype "bidirectional"))
      (node (ref "LED9") (pin "6") (pinfunction "BLUE_6") (pintype "bidirectional"))
      (node (ref "R10") (pin "2") (pinfunction "2_2") (pintype "passive"))
      (node (ref "R11") (pin "2") (pinfunction "2_2") (pintype "passive"))
      (node (ref "R12") (pin "2") (pinfunction "2_2") (pintype "passive"))
      (node (ref "R13") (pin "2") (pinfunction "2_2") (pintype "passive"))
      (node (ref "R14") (pin "2") (pinfunction "2_2") (pintype "passive"))
      (node (ref "R2") (pin "2") (pinfunction "2_2") (pintype "passive"))
      (node (ref "R7") (pin "2") (pinfunction "2_2") (pintype "passive"))
      (node (ref "R8") (pin "2") (pinfunction "2_2") (pintype "passive"))
      (node (ref "U$1") (pin "P$43") (pinfunction "VCC1_P$43") (pintype "bidirectional"))
      (node (ref "U$1") (pin "P$44") (pinfunction "VCC2_P$44") (pintype "bidirectional"))
      (node (ref "U$30") (pin "28") (pinfunction "VCC_28") (pintype "bidirectional"))
      (node (ref "U$33") (pin "2") (pinfunction "A0_2") (pintype "bidirectional"))
      (node (ref "U$33") (pin "28") (pinfunction "VCC_28") (pintype "bidirectional"))
      (node (ref "U$36") (pin "28") (pinfunction "VCC_28") (pintype "bidirectional"))
      (node (ref "U$36") (pin "3") (pinfunction "A1_3") (pintype "bidirectional"))
      (node (ref "U$51") (pin "2") (pinfunction "A0_2") (pintype "bidirectional"))
      (node (ref "U$51") (pin "28") (pinfunction "VCC_28") (pintype "bidirectional"))
      (node (ref "U$51") (pin "3") (pinfunction "A1_3") (pintype "bidirectional"))
    )
    (net (code "3") (name "12V") (class "Default")
      (node (ref "C4") (pin "+") (pinfunction "+_+") (pintype "passive"))
      (node (ref "IC1") (pin "1") (pinfunction "IN_1") (pintype "input"))
      (node (ref "X1") (pin "1") (pinfunction "KL_1") (pintype "passive"))
    )
    (net (code "4") (name "BTN1") (class "Default")
      (node (ref "R10") (pin "1") (pinfunction "1_1") (pintype "passive"))
      (node (ref "U$1") (pin "P$23") (pinfunction "PB12_P$23") (pintype "bidirectional"))
      (node (ref "U$42") (pin "PIN2") (pinfunction "PIN2_PIN2") (pintype "bidirectional"))
    )
    (net (code "5") (name "BTN2") (class "Default")
      (node (ref "R14") (pin "1") (pinfunction "1_1") (pintype "passive"))
      (node (ref "U$1") (pin "P$24") (pinfunction "PB13_P$24") (pintype "bidirectional"))
      (node (ref "U$42") (pin "PIN3") (pinfunction "PIN3_PIN3") (pintype "bidirectional"))
    )
    (net (code "6") (name "BTN3") (class "Default")
      (node (ref "R13") (pin "1") (pinfunction "1_1") (pintype "passive"))
      (node (ref "U$1") (pin "P$25") (pinfunction "PB14_P$25") (pintype "bidirectional"))
      (node (ref "U$42") (pin "PIN4") (pinfunction "PIN4_PIN4") (pintype "bidirectional"))
    )
    (net (code "7") (name "BTN4") (class "Default")
      (node (ref "R12") (pin "1") (pinfunction "1_1") (pintype "passive"))
      (node (ref "U$1") (pin "P$26") (pinfunction "PB15_P$26") (pintype "bidirectional"))
      (node (ref "U$42") (pin "PIN5") (pinfunction "PIN5_PIN5") (pintype "bidirectional"))
    )
    (net (code "8") (name "BTN5") (class "Default")
      (node (ref "R11") (pin "1") (pinfunction "1_1") (pintype "passive"))
      (node (ref "U$1") (pin "P$27") (pinfunction "PD8_P$27") (pintype "bidirectional"))
      (node (ref "U$42") (pin "PIN6") (pinfunction "PIN6_PIN6") (pintype "bidirectional"))
    )
    (net (code "9") (name "GND") (class "Default")
      (node (ref "C1") (pin "2") (pinfunction "P$2_2") (pintype "passive"))
      (node (ref "C2") (pin "2") (pinfunction "P$2_2") (pintype "passive"))
      (node (ref "C3") (pin "2") (pinfunction "P$2_2") (pintype "passive"))
      (node (ref "C4") (pin "-") (pinfunction "-_-") (pintype "passive"))
      (node (ref "C5") (pin "-") (pinfunction "-_-") (pintype "passive"))
      (node (ref "C6") (pin "2") (pinfunction "P$2_2") (pintype "passive"))
      (node (ref "C7") (pin "2") (pinfunction "P$2_2") (pintype "passive"))
      (node (ref "C8") (pin "2") (pinfunction "P$2_2") (pintype "passive"))
      (node (ref "C9") (pin "2") (pinfunction "P$2_2") (pintype "passive"))
      (node (ref "D2") (pin "A") (pinfunction "A_A") (pintype "passive"))
      (node (ref "DIS1") (pin "3") (pinfunction "CC_3") (pintype "passive"))
      (node (ref "DIS1") (pin "8") (pinfunction "CC_8") (pintype "passive"))
      (node (ref "DIS2") (pin "3") (pinfunction "CC_3") (pintype "passive"))
      (node (ref "DIS2") (pin "8") (pinfunction "CC_8") (pintype "passive"))
      (node (ref "DIS3") (pin "3") (pinfunction "CC_3") (pintype "passive"))
      (node (ref "DIS3") (pin "8") (pinfunction "CC_8") (pintype "passive"))
      (node (ref "DIS4") (pin "3") (pinfunction "CC_3") (pintype "passive"))
      (node (ref "DIS4") (pin "8") (pinfunction "CC_8") (pintype "passive"))
      (node (ref "DIS5") (pin "3") (pinfunction "CC_3") (pintype "passive"))
      (node (ref "DIS5") (pin "8") (pinfunction "CC_8") (pintype "passive"))
      (node (ref "DIS6") (pin "3") (pinfunction "CC_3") (pintype "passive"))
      (node (ref "DIS6") (pin "8") (pinfunction "CC_8") (pintype "passive"))
      (node (ref "IC1") (pin "3") (pinfunction "GND_3") (pintype "power_in"))
      (node (ref "IC1") (pin "5") (pinfunction "EN_5") (pintype "input"))
      (node (ref "IC1") (pin "6") (pinfunction "GND_6") (pintype "power_in"))
      (node (ref "IC2") (pin "13") (pinfunction "G_13") (pintype "input"))
      (node (ref "IC2") (pin "8") (pinfunction "GND_8") (pintype "power_in"))
      (node (ref "IC3") (pin "13") (pinfunction "G_13") (pintype "input"))
      (node (ref "IC3") (pin "8") (pinfunction "GND_8") (pintype "power_in"))
      (node (ref "IC4") (pin "13") (pinfunction "G_13") (pintype "input"))
      (node (ref "IC4") (pin "8") (pinfunction "GND_8") (pintype "power_in"))
      (node (ref "IC5") (pin "13") (pinfunction "G_13") (pintype "input"))
      (node (ref "IC5") (pin "8") (pinfunction "GND_8") (pintype "power_in"))
      (node (ref "IC6") (pin "13") (pinfunction "G_13") (pintype "input"))
      (node (ref "IC6") (pin "8") (pinfunction "GND_8") (pintype "power_in"))
      (node (ref "IC7") (pin "13") (pinfunction "G_13") (pintype "input"))
      (node (ref "IC7") (pin "8") (pinfunction "GND_8") (pintype "power_in"))
      (node (ref "IC8") (pin "13") (pinfunction "G_13") (pintype "input"))
      (node (ref "IC8") (pin "8") (pinfunction "GND_8") (pintype "power_in"))
      (node (ref "R15") (pin "2") (pinfunction "2_2") (pintype "passive"))
      (node (ref "R3") (pin "1") (pinfunction "1_1") (pintype "passive"))
      (node (ref "R4") (pin "2") (pinfunction "2_2") (pintype "passive"))
      (node (ref "R5") (pin "2") (pinfunction "2_2") (pintype "passive"))
      (node (ref "R6") (pin "2") (pinfunction "2_2") (pintype "passive"))
      (node (ref "U$1") (pin "P$21") (pinfunction "GND1_P$21") (pintype "bidirectional"))
      (node (ref "U$1") (pin "P$22") (pinfunction "GND2_P$22") (pintype "bidirectional"))
      (node (ref "U$1") (pin "P$41") (pinfunction "GND3_P$41") (pintype "bidirectional"))
      (node (ref "U$1") (pin "P$42") (pinfunction "GND4_P$42") (pintype "bidirectional"))
      (node (ref "U$1") (pin "P$62") (pinfunction "GND5_P$62") (pintype "bidirectional"))
      (node (ref "U$1") (pin "P$69") (pinfunction "GND6_P$69") (pintype "bidirectional"))
      (node (ref "U$1") (pin "P$70") (pinfunction "GND7_P$70") (pintype "bidirectional"))
      (node (ref "U$1") (pin "P$78") (pinfunction "GND8_P$78") (pintype "bidirectional"))
      (node (ref "U$30") (pin "10") (pinfunction "GND_10") (pintype "bidirectional"))
      (node (ref "U$30") (pin "19") (pinfunction "GND_19") (pintype "bidirectional"))
      (node (ref "U$30") (pin "2") (pinfunction "A0_2") (pintype "bidirectional"))
      (node (ref "U$30") (pin "24") (pinfunction "GND_24") (pintype "bidirectional"))
      (node (ref "U$30") (pin "3") (pinfunction "A1_3") (pintype "bidirectional"))
      (node (ref "U$30") (pin "4") (pinfunction "A2_4") (pintype "bidirectional"))
      (node (ref "U$30") (pin "5") (pinfunction "A3_5") (pintype "bidirectional"))
      (node (ref "U$33") (pin "10") (pinfunction "GND_10") (pintype "bidirectional"))
      (node (ref "U$33") (pin "19") (pinfunction "GND_19") (pintype "bidirectional"))
      (node (ref "U$33") (pin "24") (pinfunction "GND_24") (pintype "bidirectional"))
      (node (ref "U$33") (pin "3") (pinfunction "A1_3") (pintype "bidirectional"))
      (node (ref "U$33") (pin "4") (pinfunction "A2_4") (pintype "bidirectional"))
      (node (ref "U$33") (pin "5") (pinfunction "A3_5") (pintype "bidirectional"))
      (node (ref "U$36") (pin "10") (pinfunction "GND_10") (pintype "bidirectional"))
      (node (ref "U$36") (pin "19") (pinfunction "GND_19") (pintype "bidirectional"))
      (node (ref "U$36") (pin "2") (pinfunction "A0_2") (pintype "bidirectional"))
      (node (ref "U$36") (pin "24") (pinfunction "GND_24") (pintype "bidirectional"))
      (node (ref "U$36") (pin "4") (pinfunction "A2_4") (pintype "bidirectional"))
      (node (ref "U$36") (pin "5") (pinfunction "A3_5") (pintype "bidirectional"))
      (node (ref "U$42") (pin "PIN1") (pinfunction "PIN1_PIN1") (pintype "bidirectional"))
      (node (ref "U$51") (pin "10") (pinfunction "GND_10") (pintype "bidirectional"))
      (node (ref "U$51") (pin "19") (pinfunction "GND_19") (pintype "bidirectional"))
      (node (ref "U$51") (pin "24") (pinfunction "GND_24") (pintype "bidirectional"))
      (node (ref "U$51") (pin "4") (pinfunction "A2_4") (pintype "bidirectional"))
      (node (ref "U$51") (pin "5") (pinfunction "A3_5") (pintype "bidirectional"))
      (node (ref "U$9") (pin "3") (pinfunction "G1_3") (pintype "bidirectional"))
      (node (ref "U$9") (pin "8") (pinfunction "G2_8") (pintype "bidirectional"))
      (node (ref "X1") (pin "2") (pinfunction "KL_2") (pintype "passive"))
    )
    (net (code "10") (name "LATCH") (class "Default")
      (node (ref "IC2") (pin "12") (pinfunction "RCK_12") (pintype "input"))
      (node (ref "IC3") (pin "12") (pinfunction "RCK_12") (pintype "input"))
      (node (ref "IC4") (pin "12") (pinfunction "RCK_12") (pintype "input"))
      (node (ref "IC5") (pin "12") (pinfunction "RCK_12") (pintype "input"))
      (node (ref "IC6") (pin "12") (pinfunction "RCK_12") (pintype "input"))
      (node (ref "IC7") (pin "12") (pinfunction "RCK_12") (pintype "input"))
      (node (ref "IC8") (pin "12") (pinfunction "RCK_12") (pintype "input"))
      (node (ref "U$1") (pin "P$6") (pinfunction "PC4_P$6") (pintype "bidirectional"))
    )
    (net (code "11") (name "MOSI") (class "Default")
      (node (ref "IC2") (pin "14") (pinfunction "SER_14") (pintype "input"))
      (node (ref "U$1") (pin "P$5") (pinfunction "PA7_P$5") (pintype "bidirectional"))
    )
    (net (code "12") (name "Net-(DIS1-A)") (class "Default")
      (node (ref "DIS1") (pin "7") (pinfunction "A_7") (pintype "passive"))
      (node (ref "R22") (pin "1") (pinfunction "1_1") (pintype "passive"))
    )
    (net (code "13") (name "Net-(DIS1-B)") (class "Default")
      (node (ref "DIS1") (pin "6") (pinfunction "B_6") (pintype "passive"))
      (node (ref "R23") (pin "1") (pinfunction "1_1") (pintype "passive"))
    )
    (net (code "14") (name "Net-(DIS1-C)") (class "Default")
      (node (ref "DIS1") (pin "4") (pinfunction "C_4") (pintype "passive"))
      (node (ref "R24") (pin "1") (pinfunction "1_1") (pintype "passive"))
    )
    (net (code "15") (name "Net-(DIS1-D)") (class "Default")
      (node (ref "DIS1") (pin "2") (pinfunction "D_2") (pintype "passive"))
      (node (ref "R25") (pin "1") (pinfunction "1_1") (pintype "passive"))
    )
    (net (code "16") (name "Net-(DIS1-DP)") (class "Default")
      (node (ref "DIS1") (pin "5") (pinfunction "DP_5") (pintype "passive"))
      (node (ref "R29") (pin "1") (pinfunction "1_1") (pintype "passive"))
    )
    (net (code "17") (name "Net-(DIS1-E)") (class "Default")
      (node (ref "DIS1") (pin "1") (pinfunction "E_1") (pintype "passive"))
      (node (ref "R26") (pin "1") (pinfunction "1_1") (pintype "passive"))
    )
    (net (code "18") (name "Net-(DIS1-F)") (class "Default")
      (node (ref "DIS1") (pin "9") (pinfunction "F_9") (pintype "passive"))
      (node (ref "R27") (pin "1") (pinfunction "1_1") (pintype "passive"))
    )
    (net (code "19") (name "Net-(DIS1-G)") (class "Default")
      (node (ref "DIS1") (pin "10") (pinfunction "G_10") (pintype "passive"))
      (node (ref "R28") (pin "1") (pinfunction "1_1") (pintype "passive"))
    )
    (net (code "20") (name "Net-(DIS2-A)") (class "Default")
      (node (ref "DIS2") (pin "7") (pinfunction "A_7") (pintype "passive"))
      (node (ref "R30") (pin "1") (pinfunction "1_1") (pintype "passive"))
    )
    (net (code "21") (name "Net-(DIS2-B)") (class "Default")
      (node (ref "DIS2") (pin "6") (pinfunction "B_6") (pintype "passive"))
      (node (ref "R31") (pin "1") (pinfunction "1_1") (pintype "passive"))
    )
    (net (code "22") (name "Net-(DIS2-C)") (class "Default")
      (node (ref "DIS2") (pin "4") (pinfunction "C_4") (pintype "passive"))
      (node (ref "R32") (pin "1") (pinfunction "1_1") (pintype "passive"))
    )
    (net (code "23") (name "Net-(DIS2-D)") (class "Default")
      (node (ref "DIS2") (pin "2") (pinfunction "D_2") (pintype "passive"))
      (node (ref "R33") (pin "1") (pinfunction "1_1") (pintype "passive"))
    )
    (net (code "24") (name "Net-(DIS2-DP)") (class "Default")
      (node (ref "DIS2") (pin "5") (pinfunction "DP_5") (pintype "passive"))
      (node (ref "R37") (pin "1") (pinfunction "1_1") (pintype "passive"))
    )
    (net (code "25") (name "Net-(DIS2-E)") (class "Default")
      (node (ref "DIS2") (pin "1") (pinfunction "E_1") (pintype "passive"))
      (node (ref "R34") (pin "1") (pinfunction "1_1") (pintype "passive"))
    )
    (net (code "26") (name "Net-(DIS2-F)") (class "Default")
      (node (ref "DIS2") (pin "9") (pinfunction "F_9") (pintype "passive"))
      (node (ref "R35") (pin "1") (pinfunction "1_1") (pintype "passive"))
    )
    (net (code "27") (name "Net-(DIS2-G)") (class "Default")
      (node (ref "DIS2") (pin "10") (pinfunction "G_10") (pintype "passive"))
      (node (ref "R36") (pin "1") (pinfunction "1_1") (pintype "passive"))
    )
    (net (code "28") (name "Net-(DIS3-A)") (class "Default")
      (node (ref "DIS3") (pin "7") (pinfunction "A_7") (pintype "passive"))
      (node (ref "R38") (pin "1") (pinfunction "1_1") (pintype "passive"))
    )
    (net (code "29") (name "Net-(DIS3-B)") (class "Default")
      (node (ref "DIS3") (pin "6") (pinfunction "B_6") (pintype "passive"))
      (node (ref "R39") (pin "1") (pinfunction "1_1") (pintype "passive"))
    )
    (net (code "30") (name "Net-(DIS3-C)") (class "Default")
      (node (ref "DIS3") (pin "4") (pinfunction "C_4") (pintype "passive"))
      (node (ref "R40") (pin "1") (pinfunction "1_1") (pintype "passive"))
    )
    (net (code "31") (name "Net-(DIS3-D)") (class "Default")
      (node (ref "DIS3") (pin "2") (pinfunction "D_2") (pintype "passive"))
      (node (ref "R41") (pin "1") (pinfunction "1_1") (pintype "passive"))
    )
    (net (code "32") (name "Net-(DIS3-DP)") (class "Default")
      (node (ref "DIS3") (pin "5") (pinfunction "DP_5") (pintype "passive"))
      (node (ref "R45") (pin "1") (pinfunction "1_1") (pintype "passive"))
    )
    (net (code "33") (name "Net-(DIS3-E)") (class "Default")
      (node (ref "DIS3") (pin "1") (pinfunction "E_1") (pintype "passive"))
      (node (ref "R42") (pin "1") (pinfunction "1_1") (pintype "passive"))
    )
    (net (code "34") (name "Net-(DIS3-F)") (class "Default")
      (node (ref "DIS3") (pin "9") (pinfunction "F_9") (pintype "passive"))
      (node (ref "R43") (pin "1") (pinfunction "1_1") (pintype "passive"))
    )
    (net (code "35") (name "Net-(DIS3-G)") (class "Default")
      (node (ref "DIS3") (pin "10") (pinfunction "G_10") (pintype "passive"))
      (node (ref "R44") (pin "1") (pinfunction "1_1") (pintype "passive"))
    )
    (net (code "36") (name "Net-(DIS4-A)") (class "Default")
      (node (ref "DIS4") (pin "7") (pinfunction "A_7") (pintype "passive"))
      (node (ref "R46") (pin "1") (pinfunction "1_1") (pintype "passive"))
    )
    (net (code "37") (name "Net-(DIS4-B)") (class "Default")
      (node (ref "DIS4") (pin "6") (pinfunction "B_6") (pintype "passive"))
      (node (ref "R47") (pin "1") (pinfunction "1_1") (pintype "passive"))
    )
    (net (code "38") (name "Net-(DIS4-C)") (class "Default")
      (node (ref "DIS4") (pin "4") (pinfunction "C_4") (pintype "passive"))
      (node (ref "R48") (pin "1") (pinfunction "1_1") (pintype "passive"))
    )
    (net (code "39") (name "Net-(DIS4-D)") (class "Default")
      (node (ref "DIS4") (pin "2") (pinfunction "D_2") (pintype "passive"))
      (node (ref "R49") (pin "1") (pinfunction "1_1") (pintype "passive"))
    )
    (net (code "40") (name "Net-(DIS4-DP)") (class "Default")
      (node (ref "DIS4") (pin "5") (pinfunction "DP_5") (pintype "passive"))
      (node (ref "R53") (pin "1") (pinfunction "1_1") (pintype "passive"))
    )
    (net (code "41") (name "Net-(DIS4-E)") (class "Default")
      (node (ref "DIS4") (pin "1") (pinfunction "E_1") (pintype "passive"))
      (node (ref "R50") (pin "1") (pinfunction "1_1") (pintype "passive"))
    )
    (net (code "42") (name "Net-(DIS4-F)") (class "Default")
      (node (ref "DIS4") (pin "9") (pinfunction "F_9") (pintype "passive"))
      (node (ref "R51") (pin "1") (pinfunction "1_1") (pintype "passive"))
    )
    (net (code "43") (name "Net-(DIS4-G)") (class "Default")
      (node (ref "DIS4") (pin "10") (pinfunction "G_10") (pintype "passive"))
      (node (ref "R52") (pin "1") (pinfunction "1_1") (pintype "passive"))
    )
    (net (code "44") (name "Net-(DIS5-A)") (class "Default")
      (node (ref "DIS5") (pin "7") (pinfunction "A_7") (pintype "passive"))
      (node (ref "R54") (pin "1") (pinfunction "1_1") (pintype "passive"))
    )
    (net (code "45") (name "Net-(DIS5-B)") (class "Default")
      (node (ref "DIS5") (pin "6") (pinfunction "B_6") (pintype "passive"))
      (node (ref "R55") (pin "1") (pinfunction "1_1") (pintype "passive"))
    )
    (net (code "46") (name "Net-(DIS5-C)") (class "Default")
      (node (ref "DIS5") (pin "4") (pinfunction "C_4") (pintype "passive"))
      (node (ref "R56") (pin "1") (pinfunction "1_1") (pintype "passive"))
    )
    (net (code "47") (name "Net-(DIS5-D)") (class "Default")
      (node (ref "DIS5") (pin "2") (pinfunction "D_2") (pintype "passive"))
      (node (ref "R57") (pin "1") (pinfunction "1_1") (pintype "passive"))
    )
    (net (code "48") (name "Net-(DIS5-DP)") (class "Default")
      (node (ref "DIS5") (pin "5") (pinfunction "DP_5") (pintype "passive"))
      (node (ref "R61") (pin "1") (pinfunction "1_1") (pintype "passive"))
    )
    (net (code "49") (name "Net-(DIS5-E)") (class "Default")
      (node (ref "DIS5") (pin "1") (pinfunction "E_1") (pintype "passive"))
      (node (ref "R58") (pin "1") (pinfunction "1_1") (pintype "passive"))
    )
    (net (code "50") (name "Net-(DIS5-F)") (class "Default")
      (node (ref "DIS5") (pin "9") (pinfunction "F_9") (pintype "passive"))
      (node (ref "R59") (pin "1") (pinfunction "1_1") (pintype "passive"))
    )
    (net (code "51") (name "Net-(DIS5-G)") (class "Default")
      (node (ref "DIS5") (pin "10") (pinfunction "G_10") (pintype "passive"))
      (node (ref "R60") (pin "1") (pinfunction "1_1") (pintype "passive"))
    )
    (net (code "52") (name "Net-(DIS6-A)") (class "Default")
      (node (ref "DIS6") (pin "7") (pinfunction "A_7") (pintype "passive"))
      (node (ref "R62") (pin "1") (pinfunction "1_1") (pintype "passive"))
    )
    (net (code "53") (name "Net-(DIS6-B)") (class "Default")
      (node (ref "DIS6") (pin "6") (pinfunction "B_6") (pintype "passive"))
      (node (ref "R63") (pin "1") (pinfunction "1_1") (pintype "passive"))
    )
    (net (code "54") (name "Net-(DIS6-C)") (class "Default")
      (node (ref "DIS6") (pin "4") (pinfunction "C_4") (pintype "passive"))
      (node (ref "R64") (pin "1") (pinfunction "1_1") (pintype "passive"))
    )
    (net (code "55") (name "Net-(DIS6-D)") (class "Default")
      (node (ref "DIS6") (pin "2") (pinfunction "D_2") (pintype "passive"))
      (node (ref "R65") (pin "1") (pinfunction "1_1") (pintype "passive"))
    )
    (net (code "56") (name "Net-(DIS6-DP)") (class "Default")
      (node (ref "DIS6") (pin "5") (pinfunction "DP_5") (pintype "passive"))
      (node (ref "R69") (pin "1") (pinfunction "1_1") (pintype "passive"))
    )
    (net (code "57") (name "Net-(DIS6-E)") (class "Default")
      (node (ref "DIS6") (pin "1") (pinfunction "E_1") (pintype "passive"))
      (node (ref "R66") (pin "1") (pinfunction "1_1") (pintype "passive"))
    )
    (net (code "58") (name "Net-(DIS6-F)") (class "Default")
      (node (ref "DIS6") (pin "9") (pinfunction "F_9") (pintype "passive"))
      (node (ref "R67") (pin "1") (pinfunction "1_1") (pintype "passive"))
    )
    (net (code "59") (name "Net-(DIS6-G)") (class "Default")
      (node (ref "DIS6") (pin "10") (pinfunction "G_10") (pintype "passive"))
      (node (ref "R68") (pin "1") (pinfunction "1_1") (pintype "passive"))
    )
    (net (code "60") (name "Net-(IC1-FB)") (class "Default")
      (node (ref "IC1") (pin "4") (pinfunction "FB_4") (pintype "input"))
      (node (ref "R2") (pin "1") (pinfunction "1_1") (pintype "passive"))
      (node (ref "R3") (pin "2") (pinfunction "2_2") (pintype "passive"))
    )
    (net (code "61") (name "Net-(IC1-OUT)") (class "Default")
      (node (ref "D2") (pin "C") (pinfunction "C_C") (pintype "passive"))
      (node (ref "IC1") (pin "2") (pinfunction "OUT_2") (pintype "output"))
      (node (ref "L2") (pin "1") (pinfunction "1_1") (pintype "passive"))
    )
    (net (code "62") (name "Net-(IC2A-QA)") (class "Default")
      (node (ref "IC2") (pin "15") (pinfunction "QA_15") (pintype "tri_state"))
      (node (ref "R1") (pin "2") (pinfunction "2_2") (pintype "passive"))
    )
    (net (code "63") (name "Net-(IC2A-QB)") (class "Default")
      (node (ref "IC2") (pin "1") (pinfunction "QB_1") (pintype "tri_state"))
      (node (ref "R9") (pin "2") (pinfunction "2_2") (pintype "passive"))
    )
    (net (code "64") (name "Net-(IC2A-QC)") (class "Default")
      (node (ref "IC2") (pin "2") (pinfunction "QC_2") (pintype "tri_state"))
      (node (ref "R16") (pin "2") (pinfunction "2_2") (pintype "passive"))
    )
    (net (code "65") (name "Net-(IC2A-QD)") (class "Default")
      (node (ref "IC2") (pin "3") (pinfunction "QD_3") (pintype "tri_state"))
      (node (ref "R17") (pin "2") (pinfunction "2_2") (pintype "passive"))
    )
    (net (code "66") (name "Net-(IC2A-QE)") (class "Default")
      (node (ref "IC2") (pin "4") (pinfunction "QE_4") (pintype "tri_state"))
      (node (ref "R18") (pin "2") (pinfunction "2_2") (pintype "passive"))
    )
    (net (code "67") (name "Net-(IC2A-QF)") (class "Default")
      (node (ref "IC2") (pin "5") (pinfunction "QF_5") (pintype "tri_state"))
      (node (ref "R19") (pin "2") (pinfunction "2_2") (pintype "passive"))
    )
    (net (code "68") (name "Net-(IC2A-QG)") (class "Default")
      (node (ref "IC2") (pin "6") (pinfunction "QG_6") (pintype "tri_state"))
      (node (ref "R20") (pin "2") (pinfunction "2_2") (pintype "passive"))
    )
    (net (code "69") (name "Net-(IC2A-QH)") (class "Default")
      (node (ref "IC2") (pin "7") (pinfunction "QH_7") (pintype "tri_state"))
      (node (ref "R21") (pin "2") (pinfunction "2_2") (pintype "passive"))
    )
    (net (code "70") (name "Net-(IC2A-QH*)") (class "Default")
      (node (ref "IC2") (pin "9") (pinfunction "QH*_9") (pintype "tri_state"))
      (node (ref "IC3") (pin "14") (pinfunction "SER_14") (pintype "input"))
    )
    (net (code "71") (name "Net-(IC3A-QA)") (class "Default")
      (node (ref "IC3") (pin "15") (pinfunction "QA_15") (pintype "tri_state"))
      (node (ref "R22") (pin "2") (pinfunction "2_2") (pintype "passive"))
    )
    (net (code "72") (name "Net-(IC3A-QB)") (class "Default")
      (node (ref "IC3") (pin "1") (pinfunction "QB_1") (pintype "tri_state"))
      (node (ref "R23") (pin "2") (pinfunction "2_2") (pintype "passive"))
    )
    (net (code "73") (name "Net-(IC3A-QC)") (class "Default")
      (node (ref "IC3") (pin "2") (pinfunction "QC_2") (pintype "tri_state"))
      (node (ref "R24") (pin "2") (pinfunction "2_2") (pintype "passive"))
    )
    (net (code "74") (name "Net-(IC3A-QD)") (class "Default")
      (node (ref "IC3") (pin "3") (pinfunction "QD_3") (pintype "tri_state"))
      (node (ref "R25") (pin "2") (pinfunction "2_2") (pintype "passive"))
    )
    (net (code "75") (name "Net-(IC3A-QE)") (class "Default")
      (node (ref "IC3") (pin "4") (pinfunction "QE_4") (pintype "tri_state"))
      (node (ref "R26") (pin "2") (pinfunction "2_2") (pintype "passive"))
    )
    (net (code "76") (name "Net-(IC3A-QF)") (class "Default")
      (node (ref "IC3") (pin "5") (pinfunction "QF_5") (pintype "tri_state"))
      (node (ref "R27") (pin "2") (pinfunction "2_2") (pintype "passive"))
    )
    (net (code "77") (name "Net-(IC3A-QG)") (class "Default")
      (node (ref "IC3") (pin "6") (pinfunction "QG_6") (pintype "tri_state"))
      (node (ref "R28") (pin "2") (pinfunction "2_2") (pintype "passive"))
    )
    (net (code "78") (name "Net-(IC3A-QH)") (class "Default")
      (node (ref "IC3") (pin "7") (pinfunction "QH_7") (pintype "tri_state"))
      (node (ref "R29") (pin "2") (pinfunction "2_2") (pintype "passive"))
    )
    (net (code "79") (name "Net-(IC3A-QH*)") (class "Default")
      (node (ref "IC3") (pin "9") (pinfunction "QH*_9") (pintype "tri_state"))
      (node (ref "IC4") (pin "14") (pinfunction "SER_14") (pintype "input"))
    )
    (net (code "80") (name "Net-(IC4A-QA)") (class "Default")
      (node (ref "IC4") (pin "15") (pinfunction "QA_15") (pintype "tri_state"))
      (node (ref "R30") (pin "2") (pinfunction "2_2") (pintype "passive"))
    )
    (net (code "81") (name "Net-(IC4A-QB)") (class "Default")
      (node (ref "IC4") (pin "1") (pinfunction "QB_1") (pintype "tri_state"))
      (node (ref "R31") (pin "2") (pinfunction "2_2") (pintype "passive"))
    )
    (net (code "82") (name "Net-(IC4A-QC)") (class "Default")
      (node (ref "IC4") (pin "2") (pinfunction "QC_2") (pintype "tri_state"))
      (node (ref "R32") (pin "2") (pinfunction "2_2") (pintype "passive"))
    )
    (net (code "83") (name "Net-(IC4A-QD)") (class "Default")
      (node (ref "IC4") (pin "3") (pinfunction "QD_3") (pintype "tri_state"))
      (node (ref "R33") (pin "2") (pinfunction "2_2") (pintype "passive"))
    )
    (net (code "84") (name "Net-(IC4A-QE)") (class "Default")
      (node (ref "IC4") (pin "4") (pinfunction "QE_4") (pintype "tri_state"))
      (node (ref "R34") (pin "2") (pinfunction "2_2") (pintype "passive"))
    )
    (net (code "85") (name "Net-(IC4A-QF)") (class "Default")
      (node (ref "IC4") (pin "5") (pinfunction "QF_5") (pintype "tri_state"))
      (node (ref "R35") (pin "2") (pinfunction "2_2") (pintype "passive"))
    )
    (net (code "86") (name "Net-(IC4A-QG)") (class "Default")
      (node (ref "IC4") (pin "6") (pinfunction "QG_6") (pintype "tri_state"))
      (node (ref "R36") (pin "2") (pinfunction "2_2") (pintype "passive"))
    )
    (net (code "87") (name "Net-(IC4A-QH)") (class "Default")
      (node (ref "IC4") (pin "7") (pinfunction "QH_7") (pintype "tri_state"))
      (node (ref "R37") (pin "2") (pinfunction "2_2") (pintype "passive"))
    )
    (net (code "88") (name "Net-(IC4A-QH*)") (class "Default")
      (node (ref "IC4") (pin "9") (pinfunction "QH*_9") (pintype "tri_state"))
      (node (ref "IC5") (pin "14") (pinfunction "SER_14") (pintype "input"))
    )
    (net (code "89") (name "Net-(IC5A-QA)") (class "Default")
      (node (ref "IC5") (pin "15") (pinfunction "QA_15") (pintype "tri_state"))
      (node (ref "R38") (pin "2") (pinfunction "2_2") (pintype "passive"))
    )
    (net (code "90") (name "Net-(IC5A-QB)") (class "Default")
      (node (ref "IC5") (pin "1") (pinfunction "QB_1") (pintype "tri_state"))
      (node (ref "R39") (pin "2") (pinfunction "2_2") (pintype "passive"))
    )
    (net (code "91") (name "Net-(IC5A-QC)") (class "Default")
      (node (ref "IC5") (pin "2") (pinfunction "QC_2") (pintype "tri_state"))
      (node (ref "R40") (pin "2") (pinfunction "2_2") (pintype "passive"))
    )
    (net (code "92") (name "Net-(IC5A-QD)") (class "Default")
      (node (ref "IC5") (pin "3") (pinfunction "QD_3") (pintype "tri_state"))
      (node (ref "R41") (pin "2") (pinfunction "2_2") (pintype "passive"))
    )
    (net (code "93") (name "Net-(IC5A-QE)") (class "Default")
      (node (ref "IC5") (pin "4") (pinfunction "QE_4") (pintype "tri_state"))
      (node (ref "R42") (pin "2") (pinfunction "2_2") (pintype "passive"))
    )
    (net (code "94") (name "Net-(IC5A-QF)") (class "Default")
      (node (ref "IC5") (pin "5") (pinfunction "QF_5") (pintype "tri_state"))
      (node (ref "R43") (pin "2") (pinfunction "2_2") (pintype "passive"))
    )
    (net (code "95") (name "Net-(IC5A-QG)") (class "Default")
      (node (ref "IC5") (pin "6") (pinfunction "QG_6") (pintype "tri_state"))
      (node (ref "R44") (pin "2") (pinfunction "2_2") (pintype "passive"))
    )
    (net (code "96") (name "Net-(IC5A-QH)") (class "Default")
      (node (ref "IC5") (pin "7") (pinfunction "QH_7") (pintype "tri_state"))
      (node (ref "R45") (pin "2") (pinfunction "2_2") (pintype "passive"))
    )
    (net (code "97") (name "Net-(IC5A-QH*)") (class "Default")
      (node (ref "IC5") (pin "9") (pinfunction "QH*_9") (pintype "tri_state"))
      (node (ref "IC6") (pin "14") (pinfunction "SER_14") (pintype "input"))
    )
    (net (code "98") (name "Net-(IC6A-QA)") (class "Default")
      (node (ref "IC6") (pin "15") (pinfunction "QA_15") (pintype "tri_state"))
      (node (ref "R46") (pin "2") (pinfunction "2_2") (pintype "passive"))
    )
    (net (code "99") (name "Net-(IC6A-QB)") (class "Default")
      (node (ref "IC6") (pin "1") (pinfunction "QB_1") (pintype "tri_state"))
      (node (ref "R47") (pin "2") (pinfunction "2_2") (pintype "passive"))
    )
    (net (code "100") (name "Net-(IC6A-QC)") (class "Default")
      (node (ref "IC6") (pin "2") (pinfunction "QC_2") (pintype "tri_state"))
      (node (ref "R48") (pin "2") (pinfunction "2_2") (pintype "passive"))
    )
    (net (code "101") (name "Net-(IC6A-QD)") (class "Default")
      (node (ref "IC6") (pin "3") (pinfunction "QD_3") (pintype "tri_state"))
      (node (ref "R49") (pin "2") (pinfunction "2_2") (pintype "passive"))
    )
    (net (code "102") (name "Net-(IC6A-QE)") (class "Default")
      (node (ref "IC6") (pin "4") (pinfunction "QE_4") (pintype "tri_state"))
      (node (ref "R50") (pin "2") (pinfunction "2_2") (pintype "passive"))
    )
    (net (code "103") (name "Net-(IC6A-QF)") (class "Default")
      (node (ref "IC6") (pin "5") (pinfunction "QF_5") (pintype "tri_state"))
      (node (ref "R51") (pin "2") (pinfunction "2_2") (pintype "passive"))
    )
    (net (code "104") (name "Net-(IC6A-QG)") (class "Default")
      (node (ref "IC6") (pin "6") (pinfunction "QG_6") (pintype "tri_state"))
      (node (ref "R52") (pin "2") (pinfunction "2_2") (pintype "passive"))
    )
    (net (code "105") (name "Net-(IC6A-QH)") (class "Default")
      (node (ref "IC6") (pin "7") (pinfunction "QH_7") (pintype "tri_state"))
      (node (ref "R53") (pin "2") (pinfunction "2_2") (pintype "passive"))
    )
    (net (code "106") (name "Net-(IC6A-QH*)") (class "Default")
      (node (ref "IC6") (pin "9") (pinfunction "QH*_9") (pintype "tri_state"))
      (node (ref "IC7") (pin "14") (pinfunction "SER_14") (pintype "input"))
    )
    (net (code "107") (name "Net-(IC7A-QA)") (class "Default")
      (node (ref "IC7") (pin "15") (pinfunction "QA_15") (pintype "tri_state"))
      (node (ref "R54") (pin "2") (pinfunction "2_2") (pintype "passive"))
    )
    (net (code "108") (name "Net-(IC7A-QB)") (class "Default")
      (node (ref "IC7") (pin "1") (pinfunction "QB_1") (pintype "tri_state"))
      (node (ref "R55") (pin "2") (pinfunction "2_2") (pintype "passive"))
    )
    (net (code "109") (name "Net-(IC7A-QC)") (class "Default")
      (node (ref "IC7") (pin "2") (pinfunction "QC_2") (pintype "tri_state"))
      (node (ref "R56") (pin "2") (pinfunction "2_2") (pintype "passive"))
    )
    (net (code "110") (name "Net-(IC7A-QD)") (class "Default")
      (node (ref "IC7") (pin "3") (pinfunction "QD_3") (pintype "tri_state"))
      (node (ref "R57") (pin "2") (pinfunction "2_2") (pintype "passive"))
    )
    (net (code "111") (name "Net-(IC7A-QE)") (class "Default")
      (node (ref "IC7") (pin "4") (pinfunction "QE_4") (pintype "tri_state"))
      (node (ref "R58") (pin "2") (pinfunction "2_2") (pintype "passive"))
    )
    (net (code "112") (name "Net-(IC7A-QF)") (class "Default")
      (node (ref "IC7") (pin "5") (pinfunction "QF_5") (pintype "tri_state"))
      (node (ref "R59") (pin "2") (pinfunction "2_2") (pintype "passive"))
    )
    (net (code "113") (name "Net-(IC7A-QG)") (class "Default")
      (node (ref "IC7") (pin "6") (pinfunction "QG_6") (pintype "tri_state"))
      (node (ref "R60") (pin "2") (pinfunction "2_2") (pintype "passive"))
    )
    (net (code "114") (name "Net-(IC7A-QH)") (class "Default")
      (node (ref "IC7") (pin "7") (pinfunction "QH_7") (pintype "tri_state"))
      (node (ref "R61") (pin "2") (pinfunction "2_2") (pintype "passive"))
    )
    (net (code "115") (name "Net-(IC7A-QH*)") (class "Default")
      (node (ref "IC7") (pin "9") (pinfunction "QH*_9") (pintype "tri_state"))
      (node (ref "IC8") (pin "14") (pinfunction "SER_14") (pintype "input"))
    )
    (net (code "116") (name "Net-(IC8A-QA)") (class "Default")
      (node (ref "IC8") (pin "15") (pinfunction "QA_15") (pintype "tri_state"))
      (node (ref "R62") (pin "2") (pinfunction "2_2") (pintype "passive"))
    )
    (net (code "117") (name "Net-(IC8A-QB)") (class "Default")
      (node (ref "IC8") (pin "1") (pinfunction "QB_1") (pintype "tri_state"))
      (node (ref "R63") (pin "2") (pinfunction "2_2") (pintype "passive"))
    )
    (net (code "118") (name "Net-(IC8A-QC)") (class "Default")
      (node (ref "IC8") (pin "2") (pinfunction "QC_2") (pintype "tri_state"))
      (node (ref "R64") (pin "2") (pinfunction "2_2") (pintype "passive"))
    )
    (net (code "119") (name "Net-(IC8A-QD)") (class "Default")
      (node (ref "IC8") (pin "3") (pinfunction "QD_3") (pintype "tri_state"))
      (node (ref "R65") (pin "2") (pinfunction "2_2") (pintype "passive"))
    )
    (net (code "120") (name "Net-(IC8A-QE)") (class "Default")
      (node (ref "IC8") (pin "4") (pinfunction "QE_4") (pintype "tri_state"))
      (node (ref "R66") (pin "2") (pinfunction "2_2") (pintype "passive"))
    )
    (net (code "121") (name "Net-(IC8A-QF)") (class "Default")
      (node (ref "IC8") (pin "5") (pinfunction "QF_5") (pintype "tri_state"))
      (node (ref "R67") (pin "2") (pinfunction "2_2") (pintype "passive"))
    )
    (net (code "122") (name "Net-(IC8A-QG)") (class "Default")
      (node (ref "IC8") (pin "6") (pinfunction "QG_6") (pintype "tri_state"))
      (node (ref "R68") (pin "2") (pinfunction "2_2") (pintype "passive"))
    )
    (net (code "123") (name "Net-(IC8A-QH)") (class "Default")
      (node (ref "IC8") (pin "7") (pinfunction "QH_7") (pintype "tri_state"))
      (node (ref "R69") (pin "2") (pinfunction "2_2") (pintype "passive"))
    )
    (net (code "124") (name "Net-(LED1-BGND)") (class "Default")
      (node (ref "LED1") (pin "1") (pinfunction "BGND_1") (pintype "power_in"))
      (node (ref "U$30") (pin "8") (pinfunction "/OUT2_8") (pintype "bidirectional"))
    )
    (net (code "125") (name "Net-(LED1-GGND)") (class "Default")
      (node (ref "LED1") (pin "2") (pinfunction "GGND_2") (pintype "power_in"))
      (node (ref "U$30") (pin "7") (pinfunction "/OUT1_7") (pintype "bidirectional"))
    )
    (net (code "126") (name "Net-(LED1-RGND)") (class "Default")
      (node (ref "LED1") (pin "3") (pinfunction "RGND_3") (pintype "power_in"))
      (node (ref "U$30") (pin "6") (pinfunction "/OUT0_6") (pintype "bidirectional"))
    )
    (net (code "127") (name "Net-(LED2-BGND)") (class "Default")
      (node (ref "LED2") (pin "1") (pinfunction "BGND_1") (pintype "power_in"))
      (node (ref "U$30") (pin "12") (pinfunction "/OUT5_12") (pintype "bidirectional"))
    )
    (net (code "128") (name "Net-(LED2-GGND)") (class "Default")
      (node (ref "LED2") (pin "2") (pinfunction "GGND_2") (pintype "power_in"))
      (node (ref "U$30") (pin "11") (pinfunction "/OUT4_11") (pintype "bidirectional"))
    )
    (net (code "129") (name "Net-(LED2-RGND)") (class "Default")
      (node (ref "LED2") (pin "3") (pinfunction "RGND_3") (pintype "power_in"))
      (node (ref "U$30") (pin "9") (pinfunction "/OUT3_9") (pintype "bidirectional"))
    )
    (net (code "130") (name "Net-(LED3-BGND)") (class "Default")
      (node (ref "LED3") (pin "1") (pinfunction "BGND_1") (pintype "power_in"))
      (node (ref "U$30") (pin "15") (pinfunction "/OUT8_15") (pintype "bidirectional"))
    )
    (net (code "131") (name "Net-(LED3-GGND)") (class "Default")
      (node (ref "LED3") (pin "2") (pinfunction "GGND_2") (pintype "power_in"))
      (node (ref "U$30") (pin "14") (pinfunction "/OUT7_14") (pintype "bidirectional"))
    )
    (net (code "132") (name "Net-(LED3-RGND)") (class "Default")
      (node (ref "LED3") (pin "3") (pinfunction "RGND_3") (pintype "power_in"))
      (node (ref "U$30") (pin "13") (pinfunction "/OUT6_13") (pintype "bidirectional"))
    )
    (net (code "133") (name "Net-(LED4-BGND)") (class "Default")
      (node (ref "LED4") (pin "1") (pinfunction "BGND_1") (pintype "power_in"))
      (node (ref "U$30") (pin "18") (pinfunction "/OUT11_18") (pintype "bidirectional"))
    )
    (net (code "134") (name "Net-(LED4-GGND)") (class "Default")
      (node (ref "LED4") (pin "2") (pinfunction "GGND_2") (pintype "power_in"))
      (node (ref "U$30") (pin "17") (pinfunction "/OUT10_17") (pintype "bidirectional"))
    )
    (net (code "135") (name "Net-(LED4-RGND)") (class "Default")
      (node (ref "LED4") (pin "3") (pinfunction "RGND_3") (pintype "power_in"))
      (node (ref "U$30") (pin "16") (pinfunction "/OUT9_16") (pintype "bidirectional"))
    )
    (net (code "136") (name "Net-(LED5-BGND)") (class "Default")
      (node (ref "LED5") (pin "1") (pinfunction "BGND_1") (pintype "power_in"))
      (node (ref "U$30") (pin "22") (pinfunction "/OUT14_22") (pintype "bidirectional"))
    )
    (net (code "137") (name "Net-(LED5-GGND)") (class "Default")
      (node (ref "LED5") (pin "2") (pinfunction "GGND_2") (pintype "power_in"))
      (node (ref "U$30") (pin "21") (pinfunction "/OUT13_21") (pintype "bidirectional"))
    )
    (net (code "138") (name "Net-(LED5-RGND)") (class "Default")
      (node (ref "LED5") (pin "3") (pinfunction "RGND_3") (pintype "power_in"))
      (node (ref "U$30") (pin "20") (pinfunction "/OUT12_20") (pintype "bidirectional"))
    )
    (net (code "139") (name "Net-(LED6-BGND)") (class "Default")
      (node (ref "LED6") (pin "1") (pinfunction "BGND_1") (pintype "power_in"))
      (node (ref "U$33") (pin "8") (pinfunction "/OUT2_8") (pintype "bidirectional"))
    )
    (net (code "140") (name "Net-(LED6-GGND)") (class "Default")
      (node (ref "LED6") (pin "2") (pinfunction "GGND_2") (pintype "power_in"))
      (node (ref "U$33") (pin "7") (pinfunction "/OUT1_7") (pintype "bidirectional"))
    )
    (net (code "141") (name "Net-(LED6-RGND)") (class "Default")
      (node (ref "LED6") (pin "3") (pinfunction "RGND_3") (pintype "power_in"))
      (node (ref "U$33") (pin "6") (pinfunction "/OUT0_6") (pintype "bidirectional"))
    )
    (net (code "142") (name "Net-(LED7-BGND)") (class "Default")
      (node (ref "LED7") (pin "1") (pinfunction "BGND_1") (pintype "power_in"))
      (node (ref "U$33") (pin "12") (pinfunction "/OUT5_12") (pintype "bidirectional"))
    )
    (net (code "143") (name "Net-(LED7-GGND)") (class "Default")
      (node (ref "LED7") (pin "2") (pinfunction "GGND_2") (pintype "power_in"))
      (node (ref "U$33") (pin "11") (pinfunction "/OUT4_11") (pintype "bidirectional"))
    )
    (net (code "144") (name "Net-(LED7-RGND)") (class "Default")
      (node (ref "LED7") (pin "3") (pinfunction "RGND_3") (pintype "power_in"))
      (node (ref "U$33") (pin "9") (pinfunction "/OUT3_9") (pintype "bidirectional"))
    )
    (net (code "145") (name "Net-(LED8-BGND)") (class "Default")
      (node (ref "LED8") (pin "1") (pinfunction "BGND_1") (pintype "power_in"))
      (node (ref "U$33") (pin "15") (pinfunction "/OUT8_15") (pintype "bidirectional"))
    )
    (net (code "146") (name "Net-(LED8-GGND)") (class "Default")
      (node (ref "LED8") (pin "2") (pinfunction "GGND_2") (pintype "power_in"))
      (node (ref "U$33") (pin "14") (pinfunction "/OUT7_14") (pintype "bidirectional"))
    )
    (net (code "147") (name "Net-(LED8-RGND)") (class "Default")
      (node (ref "LED8") (pin "3") (pinfunction "RGND_3") (pintype "power_in"))
      (node (ref "U$33") (pin "13") (pinfunction "/OUT6_13") (pintype "bidirectional"))
    )
    (net (code "148") (name "Net-(LED9-BGND)") (class "Default")
      (node (ref "LED9") (pin "1") (pinfunction "BGND_1") (pintype "power_in"))
      (node (ref "U$33") (pin "18") (pinfunction "/OUT11_18") (pintype "bidirectional"))
    )
    (net (code "149") (name "Net-(LED9-GGND)") (class "Default")
      (node (ref "LED9") (pin "2") (pinfunction "GGND_2") (pintype "power_in"))
      (node (ref "U$33") (pin "17") (pinfunction "/OUT10_17") (pintype "bidirectional"))
    )
    (net (code "150") (name "Net-(LED9-RGND)") (class "Default")
      (node (ref "LED9") (pin "3") (pinfunction "RGND_3") (pintype "power_in"))
      (node (ref "U$33") (pin "16") (pinfunction "/OUT9_16") (pintype "bidirectional"))
    )
    (net (code "151") (name "Net-(LED10-BGND)") (class "Default")
      (node (ref "LED10") (pin "1") (pinfunction "BGND_1") (pintype "power_in"))
      (node (ref "U$33") (pin "22") (pinfunction "/OUT14_22") (pintype "bidirectional"))
    )
    (net (code "152") (name "Net-(LED10-GGND)") (class "Default")
      (node (ref "LED10") (pin "2") (pinfunction "GGND_2") (pintype "power_in"))
      (node (ref "U$33") (pin "21") (pinfunction "/OUT13_21") (pintype "bidirectional"))
    )
    (net (code "153") (name "Net-(LED10-RGND)") (class "Default")
      (node (ref "LED10") (pin "3") (pinfunction "RGND_3") (pintype "power_in"))
      (node (ref "U$33") (pin "20") (pinfunction "/OUT12_20") (pintype "bidirectional"))
    )
    (net (code "154") (name "Net-(LED11-BGND)") (class "Default")
      (node (ref "LED11") (pin "1") (pinfunction "BGND_1") (pintype "power_in"))
      (node (ref "U$36") (pin "8") (pinfunction "/OUT2_8") (pintype "bidirectional"))
    )
    (net (code "155") (name "Net-(LED11-GGND)") (class "Default")
      (node (ref "LED11") (pin "2") (pinfunction "GGND_2") (pintype "power_in"))
      (node (ref "U$36") (pin "7") (pinfunction "/OUT1_7") (pintype "bidirectional"))
    )
    (net (code "156") (name "Net-(LED11-RGND)") (class "Default")
      (node (ref "LED11") (pin "3") (pinfunction "RGND_3") (pintype "power_in"))
      (node (ref "U$36") (pin "6") (pinfunction "/OUT0_6") (pintype "bidirectional"))
    )
    (net (code "157") (name "Net-(LED12-BGND)") (class "Default")
      (node (ref "LED12") (pin "1") (pinfunction "BGND_1") (pintype "power_in"))
      (node (ref "U$36") (pin "12") (pinfunction "/OUT5_12") (pintype "bidirectional"))
    )
    (net (code "158") (name "Net-(LED12-GGND)") (class "Default")
      (node (ref "LED12") (pin "2") (pinfunction "GGND_2") (pintype "power_in"))
      (node (ref "U$36") (pin "11") (pinfunction "/OUT4_11") (pintype "bidirectional"))
    )
    (net (code "159") (name "Net-(LED12-RGND)") (class "Default")
      (node (ref "LED12") (pin "3") (pinfunction "RGND_3") (pintype "power_in"))
      (node (ref "U$36") (pin "9") (pinfunction "/OUT3_9") (pintype "bidirectional"))
    )
    (net (code "160") (name "Net-(LED13-BGND)") (class "Default")
      (node (ref "LED13") (pin "1") (pinfunction "BGND_1") (pintype "power_in"))
      (node (ref "U$36") (pin "15") (pinfunction "/OUT8_15") (pintype "bidirectional"))
    )
    (net (code "161") (name "Net-(LED13-GGND)") (class "Default")
      (node (ref "LED13") (pin "2") (pinfunction "GGND_2") (pintype "power_in"))
      (node (ref "U$36") (pin "14") (pinfunction "/OUT7_14") (pintype "bidirectional"))
    )
    (net (code "162") (name "Net-(LED13-RGND)") (class "Default")
      (node (ref "LED13") (pin "3") (pinfunction "RGND_3") (pintype "power_in"))
      (node (ref "U$36") (pin "13") (pinfunction "/OUT6_13") (pintype "bidirectional"))
    )
    (net (code "163") (name "Net-(LED14-BGND)") (class "Default")
      (node (ref "LED14") (pin "1") (pinfunction "BGND_1") (pintype "power_in"))
      (node (ref "U$36") (pin "18") (pinfunction "/OUT11_18") (pintype "bidirectional"))
    )
    (net (code "164") (name "Net-(LED14-GGND)") (class "Default")
      (node (ref "LED14") (pin "2") (pinfunction "GGND_2") (pintype "power_in"))
      (node (ref "U$36") (pin "17") (pinfunction "/OUT10_17") (pintype "bidirectional"))
    )
    (net (code "165") (name "Net-(LED14-RGND)") (class "Default")
      (node (ref "LED14") (pin "3") (pinfunction "RGND_3") (pintype "power_in"))
      (node (ref "U$36") (pin "16") (pinfunction "/OUT9_16") (pintype "bidirectional"))
    )
    (net (code "166") (name "Net-(LED15-BGND)") (class "Default")
      (node (ref "LED15") (pin "1") (pinfunction "BGND_1") (pintype "power_in"))
      (node (ref "U$36") (pin "22") (pinfunction "/OUT14_22") (pintype "bidirectional"))
    )
    (net (code "167") (name "Net-(LED15-GGND)") (class "Default")
      (node (ref "LED15") (pin "2") (pinfunction "GGND_2") (pintype "power_in"))
      (node (ref "U$36") (pin "21") (pinfunction "/OUT13_21") (pintype "bidirectional"))
    )
    (net (code "168") (name "Net-(LED15-RGND)") (class "Default")
      (node (ref "LED15") (pin "3") (pinfunction "RGND_3") (pintype "power_in"))
      (node (ref "U$36") (pin "20") (pinfunction "/OUT12_20") (pintype "bidirectional"))
    )
    (net (code "169") (name "Net-(LED16-BGND)") (class "Default")
      (node (ref "LED16") (pin "1") (pinfunction "BGND_1") (pintype "power_in"))
      (node (ref "U$51") (pin "8") (pinfunction "/OUT2_8") (pintype "bidirectional"))
    )
    (net (code "170") (name "Net-(LED16-GGND)") (class "Default")
      (node (ref "LED16") (pin "2") (pinfunction "GGND_2") (pintype "power_in"))
      (node (ref "U$51") (pin "7") (pinfunction "/OUT1_7") (pintype "bidirectional"))
    )
    (net (code "171") (name "Net-(LED16-RGND)") (class "Default")
      (node (ref "LED16") (pin "3") (pinfunction "RGND_3") (pintype "power_in"))
      (node (ref "U$51") (pin "6") (pinfunction "/OUT0_6") (pintype "bidirectional"))
    )
    (net (code "172") (name "Net-(LED17-BGND)") (class "Default")
      (node (ref "LED17") (pin "1") (pinfunction "BGND_1") (pintype "power_in"))
      (node (ref "U$51") (pin "12") (pinfunction "/OUT5_12") (pintype "bidirectional"))
    )
    (net (code "173") (name "Net-(LED17-GGND)") (class "Default")
      (node (ref "LED17") (pin "2") (pinfunction "GGND_2") (pintype "power_in"))
      (node (ref "U$51") (pin "11") (pinfunction "/OUT4_11") (pintype "bidirectional"))
    )
    (net (code "174") (name "Net-(LED17-RGND)") (class "Default")
      (node (ref "LED17") (pin "3") (pinfunction "RGND_3") (pintype "power_in"))
      (node (ref "U$51") (pin "9") (pinfunction "/OUT3_9") (pintype "bidirectional"))
    )
    (net (code "175") (name "Net-(LED18-BGND)") (class "Default")
      (node (ref "LED18") (pin "1") (pinfunction "BGND_1") (pintype "power_in"))
      (node (ref "U$51") (pin "15") (pinfunction "/OUT8_15") (pintype "bidirectional"))
    )
    (net (code "176") (name "Net-(LED18-GGND)") (class "Default")
      (node (ref "LED18") (pin "2") (pinfunction "GGND_2") (pintype "power_in"))
      (node (ref "U$51") (pin "14") (pinfunction "/OUT7_14") (pintype "bidirectional"))
    )
    (net (code "177") (name "Net-(LED18-RGND)") (class "Default")
      (node (ref "LED18") (pin "3") (pinfunction "RGND_3") (pintype "power_in"))
      (node (ref "U$51") (pin "13") (pinfunction "/OUT6_13") (pintype "bidirectional"))
    )
    (net (code "178") (name "Net-(LED19-BGND)") (class "Default")
      (node (ref "LED19") (pin "1") (pinfunction "BGND_1") (pintype "power_in"))
      (node (ref "U$51") (pin "18") (pinfunction "/OUT11_18") (pintype "bidirectional"))
    )
    (net (code "179") (name "Net-(LED19-GGND)") (class "Default")
      (node (ref "LED19") (pin "2") (pinfunction "GGND_2") (pintype "power_in"))
      (node (ref "U$51") (pin "17") (pinfunction "/OUT10_17") (pintype "bidirectional"))
    )
    (net (code "180") (name "Net-(LED19-RGND)") (class "Default")
      (node (ref "LED19") (pin "3") (pinfunction "RGND_3") (pintype "power_in"))
      (node (ref "U$51") (pin "16") (pinfunction "/OUT9_16") (pintype "bidirectional"))
    )
    (net (code "181") (name "Net-(LED20-BGND)") (class "Default")
      (node (ref "LED20") (pin "1") (pinfunction "BGND_1") (pintype "power_in"))
      (node (ref "U$51") (pin "22") (pinfunction "/OUT14_22") (pintype "bidirectional"))
    )
    (net (code "182") (name "Net-(LED20-GGND)") (class "Default")
      (node (ref "LED20") (pin "2") (pinfunction "GGND_2") (pintype "power_in"))
      (node (ref "U$51") (pin "21") (pinfunction "/OUT13_21") (pintype "bidirectional"))
    )
    (net (code "183") (name "Net-(LED20-RGND)") (class "Default")
      (node (ref "LED20") (pin "3") (pinfunction "RGND_3") (pintype "power_in"))
      (node (ref "U$51") (pin "20") (pinfunction "/OUT12_20") (pintype "bidirectional"))
    )
    (net (code "184") (name "Net-(U$9-A)") (class "Default")
      (node (ref "R1") (pin "1") (pinfunction "1_1") (pintype "passive"))
      (node (ref "U$9") (pin "7") (pinfunction "A_7") (pintype "bidirectional"))
    )
    (net (code "185") (name "Net-(U$9-B)") (class "Default")
      (node (ref "R9") (pin "1") (pinfunction "1_1") (pintype "passive"))
      (node (ref "U$9") (pin "6") (pinfunction "B_6") (pintype "bidirectional"))
    )
    (net (code "186") (name "Net-(U$9-C)") (class "Default")
      (node (ref "R16") (pin "1") (pinfunction "1_1") (pintype "passive"))
      (node (ref "U$9") (pin "4") (pinfunction "C_4") (pintype "bidirectional"))
    )
    (net (code "187") (name "Net-(U$9-D)") (class "Default")
      (node (ref "R17") (pin "1") (pinfunction "1_1") (pintype "passive"))
      (node (ref "U$9") (pin "2") (pinfunction "D_2") (pintype "bidirectional"))
    )
    (net (code "188") (name "Net-(U$9-DP)") (class "Default")
      (node (ref "R21") (pin "1") (pinfunction "1_1") (pintype "passive"))
      (node (ref "U$9") (pin "5") (pinfunction "DP_5") (pintype "bidirectional"))
    )
    (net (code "189") (name "Net-(U$9-E)") (class "Default")
      (node (ref "R18") (pin "1") (pinfunction "1_1") (pintype "passive"))
      (node (ref "U$9") (pin "1") (pinfunction "E_1") (pintype "bidirectional"))
    )
    (net (code "190") (name "Net-(U$9-F)") (class "Default")
      (node (ref "R19") (pin "1") (pinfunction "1_1") (pintype "passive"))
      (node (ref "U$9") (pin "9") (pinfunction "F_9") (pintype "bidirectional"))
    )
    (net (code "191") (name "Net-(U$9-G)") (class "Default")
      (node (ref "R20") (pin "1") (pinfunction "1_1") (pintype "passive"))
      (node (ref "U$9") (pin "10") (pinfunction "G_10") (pintype "bidirectional"))
    )
    (net (code "192") (name "Net-(U$30-REXT)") (class "Default")
      (node (ref "R4") (pin "1") (pinfunction "1_1") (pintype "passive"))
      (node (ref "U$30") (pin "1") (pinfunction "REXT_1") (pintype "bidirectional"))
    )
    (net (code "193") (name "Net-(U$33-REXT)") (class "Default")
      (node (ref "R5") (pin "1") (pinfunction "1_1") (pintype "passive"))
      (node (ref "U$33") (pin "1") (pinfunction "REXT_1") (pintype "bidirectional"))
    )
    (net (code "194") (name "Net-(U$36-REXT)") (class "Default")
      (node (ref "R6") (pin "1") (pinfunction "1_1") (pintype "passive"))
      (node (ref "U$36") (pin "1") (pinfunction "REXT_1") (pintype "bidirectional"))
    )
    (net (code "195") (name "Net-(U$51-REXT)") (class "Default")
      (node (ref "R15") (pin "1") (pinfunction "1_1") (pintype "passive"))
      (node (ref "U$51") (pin "1") (pinfunction "REXT_1") (pintype "bidirectional"))
    )
    (net (code "196") (name "SCK") (class "Default")
      (node (ref "IC2") (pin "11") (pinfunction "SCK_11") (pintype "input"))
      (node (ref "IC3") (pin "11") (pinfunction "SCK_11") (pintype "input"))
      (node (ref "IC4") (pin "11") (pinfunction "SCK_11") (pintype "input"))
      (node (ref "IC5") (pin "11") (pinfunction "SCK_11") (pintype "input"))
      (node (ref "IC6") (pin "11") (pinfunction "SCK_11") (pintype "input"))
      (node (ref "IC7") (pin "11") (pinfunction "SCK_11") (pintype "input"))
      (node (ref "IC8") (pin "11") (pinfunction "SCK_11") (pintype "input"))
      (node (ref "U$1") (pin "P$3") (pinfunction "PA5_P$3") (pintype "bidirectional"))
    )
    (net (code "197") (name "SCL") (class "Default")
      (node (ref "R8") (pin "1") (pinfunction "1_1") (pintype "passive"))
      (node (ref "U$1") (pin "P$19") (pinfunction "PB10_P$19") (pintype "bidirectional"))
      (node (ref "U$30") (pin "26") (pinfunction "SCL_26") (pintype "bidirectional"))
      (node (ref "U$33") (pin "26") (pinfunction "SCL_26") (pintype "bidirectional"))
      (node (ref "U$36") (pin "26") (pinfunction "SCL_26") (pintype "bidirectional"))
      (node (ref "U$51") (pin "26") (pinfunction "SCL_26") (pintype "bidirectional"))
    )
    (net (code "198") (name "SDA") (class "Default")
      (node (ref "R7") (pin "1") (pinfunction "1_1") (pintype "passive"))
      (node (ref "U$1") (pin "P$20") (pinfunction "PB11_P$20") (pintype "bidirectional"))
      (node (ref "U$30") (pin "27") (pinfunction "SDA_27") (pintype "bidirectional"))
      (node (ref "U$33") (pin "27") (pinfunction "SDA_27") (pintype "bidirectional"))
      (node (ref "U$36") (pin "27") (pinfunction "SDA_27") (pintype "bidirectional"))
      (node (ref "U$51") (pin "27") (pinfunction "SDA_27") (pintype "bidirectional"))
    )
    (net (code "199") (name "unconnected-(IC8A-QH*-Pad9)") (class "Default")
      (node (ref "IC8") (pin "9") (pinfunction "QH*_9") (pintype "tri_state"))
    )
    (net (code "200") (name "unconnected-(U$1A-PA4-PadP$2)") (class "Default")
      (node (ref "U$1") (pin "P$2") (pinfunction "PA4_P$2") (pintype "bidirectional"))
    )
    (net (code "201") (name "unconnected-(U$1A-PA6-PadP$4)") (class "Default")
      (node (ref "U$1") (pin "P$4") (pinfunction "PA6_P$4") (pintype "bidirectional"))
    )
    (net (code "202") (name "unconnected-(U$1A-PB0-PadP$8)") (class "Default")
      (node (ref "U$1") (pin "P$8") (pinfunction "PB0_P$8") (pintype "bidirectional"))
    )
    (net (code "203") (name "unconnected-(U$1A-PB1-PadP$9)") (class "Default")
      (node (ref "U$1") (pin "P$9") (pinfunction "PB1_P$9") (pintype "bidirectional"))
    )
    (net (code "204") (name "unconnected-(U$1A-PC5-PadP$7)") (class "Default")
      (node (ref "U$1") (pin "P$7") (pinfunction "PC5_P$7") (pintype "bidirectional"))
    )
    (net (code "205") (name "unconnected-(U$1A-PE7-PadP$10)") (class "Default")
      (node (ref "U$1") (pin "P$10") (pinfunction "PE7_P$10") (pintype "bidirectional"))
    )
    (net (code "206") (name "unconnected-(U$1A-PE8-PadP$11)") (class "Default")
      (node (ref "U$1") (pin "P$11") (pinfunction "PE8_P$11") (pintype "bidirectional"))
    )
    (net (code "207") (name "unconnected-(U$1A-PE9-PadP$12)") (class "Default")
      (node (ref "U$1") (pin "P$12") (pinfunction "PE9_P$12") (pintype "bidirectional"))
    )
    (net (code "208") (name "unconnected-(U$1A-PE10-PadP$13)") (class "Default")
      (node (ref "U$1") (pin "P$13") (pinfunction "PE10_P$13") (pintype "bidirectional"))
    )
    (net (code "209") (name "unconnected-(U$1A-PE11-PadP$14)") (class "Default")
      (node (ref "U$1") (pin "P$14") (pinfunction "PE11_P$14") (pintype "bidirectional"))
    )
    (net (code "210") (name "unconnected-(U$1A-PE12-PadP$15)") (class "Default")
      (node (ref "U$1") (pin "P$15") (pinfunction "PE12_P$15") (pintype "bidirectional"))
    )
    (net (code "211") (name "unconnected-(U$1A-PE13-PadP$16)") (class "Default")
      (node (ref "U$1") (pin "P$16") (pinfunction "PE13_P$16") (pintype "bidirectional"))
    )
    (net (code "212") (name "unconnected-(U$1A-PE14-PadP$17)") (class "Default")
      (node (ref "U$1") (pin "P$17") (pinfunction "PE14_P$17") (pintype "bidirectional"))
    )
    (net (code "213") (name "unconnected-(U$1A-PE15-PadP$18)") (class "Default")
      (node (ref "U$1") (pin "P$18") (pinfunction "PE15_P$18") (pintype "bidirectional"))
    )
    (net (code "214") (name "unconnected-(U$1B-PA8-PadP$39)") (class "Default")
      (node (ref "U$1") (pin "P$39") (pinfunction "PA8_P$39") (pintype "bidirectional"))
    )
    (net (code "215") (name "unconnected-(U$1B-PA9-PadP$40)") (class "Default")
      (node (ref "U$1") (pin "P$40") (pinfunction "PA9_P$40") (pintype "bidirectional"))
    )
    (net (code "216") (name "unconnected-(U$1B-PC6-PadP$35)") (class "Default")
      (node (ref "U$1") (pin "P$35") (pinfunction "PC6_P$35") (pintype "bidirectional"))
    )
    (net (code "217") (name "unconnected-(U$1B-PC7-PadP$36)") (class "Default")
      (node (ref "U$1") (pin "P$36") (pinfunction "PC7_P$36") (pintype "bidirectional"))
    )
    (net (code "218") (name "unconnected-(U$1B-PC8-PadP$37)") (class "Default")
      (node (ref "U$1") (pin "P$37") (pinfunction "PC8_P$37") (pintype "bidirectional"))
    )
    (net (code "219") (name "unconnected-(U$1B-PC9-PadP$38)") (class "Default")
      (node (ref "U$1") (pin "P$38") (pinfunction "PC9_P$38") (pintype "bidirectional"))
    )
    (net (code "220") (name "unconnected-(U$1B-PD9-PadP$28)") (class "Default")
      (node (ref "U$1") (pin "P$28") (pinfunction "PD9_P$28") (pintype "bidirectional"))
    )
    (net (code "221") (name "unconnected-(U$1B-PD10-PadP$29)") (class "Default")
      (node (ref "U$1") (pin "P$29") (pinfunction "PD10_P$29") (pintype "bidirectional"))
    )
    (net (code "222") (name "unconnected-(U$1B-PD11-PadP$30)") (class "Default")
      (node (ref "U$1") (pin "P$30") (pinfunction "PD11_P$30") (pintype "bidirectional"))
    )
    (net (code "223") (name "unconnected-(U$1B-PD12-PadP$31)") (class "Default")
      (node (ref "U$1") (pin "P$31") (pinfunction "PD12_P$31") (pintype "bidirectional"))
    )
    (net (code "224") (name "unconnected-(U$1B-PD13-PadP$32)") (class "Default")
      (node (ref "U$1") (pin "P$32") (pinfunction "PD13_P$32") (pintype "bidirectional"))
    )
    (net (code "225") (name "unconnected-(U$1B-PD14-PadP$33)") (class "Default")
      (node (ref "U$1") (pin "P$33") (pinfunction "PD14_P$33") (pintype "bidirectional"))
    )
    (net (code "226") (name "unconnected-(U$1B-PD15-PadP$34)") (class "Default")
      (node (ref "U$1") (pin "P$34") (pinfunction "PD15_P$34") (pintype "bidirectional"))
    )
    (net (code "227") (name "unconnected-(U$1C-PB4-PadP$54)") (class "Default")
      (node (ref "U$1") (pin "P$54") (pinfunction "PB4_P$54") (pintype "bidirectional"))
    )
    (net (code "228") (name "unconnected-(U$1C-PB5-PadP$55)") (class "Default")
      (node (ref "U$1") (pin "P$55") (pinfunction "PB5_P$55") (pintype "bidirectional"))
    )
    (net (code "229") (name "unconnected-(U$1C-PB6-PadP$56)") (class "Default")
      (node (ref "U$1") (pin "P$56") (pinfunction "PB6_P$56") (pintype "bidirectional"))
    )
    (net (code "230") (name "unconnected-(U$1C-PB7-PadP$57)") (class "Default")
      (node (ref "U$1") (pin "P$57") (pinfunction "PB7_P$57") (pintype "bidirectional"))
    )
    (net (code "231") (name "unconnected-(U$1C-PB8-PadP$58)") (class "Default")
      (node (ref "U$1") (pin "P$58") (pinfunction "PB8_P$58") (pintype "bidirectional"))
    )
    (net (code "232") (name "unconnected-(U$1C-PB9-PadP$59)") (class "Default")
      (node (ref "U$1") (pin "P$59") (pinfunction "PB9_P$59") (pintype "bidirectional"))
    )
    (net (code "233") (name "unconnected-(U$1C-PC10-PadP$45)") (class "Default")
      (node (ref "U$1") (pin "P$45") (pinfunction "PC10_P$45") (pintype "bidirectional"))
    )
    (net (code "234") (name "unconnected-(U$1C-PC11-PadP$46)") (class "Default")
      (node (ref "U$1") (pin "P$46") (pinfunction "PC11_P$46") (pintype "bidirectional"))
    )
    (net (code "235") (name "unconnected-(U$1C-PC12-PadP$47)") (class "Default")
      (node (ref "U$1") (pin "P$47") (pinfunction "PC12_P$47") (pintype "bidirectional"))
    )
    (net (code "236") (name "unconnected-(U$1C-PD2-PadP$48)") (class "Default")
      (node (ref "U$1") (pin "P$48") (pinfunction "PD2_P$48") (pintype "bidirectional"))
    )
    (net (code "237") (name "unconnected-(U$1C-PD3-PadP$49)") (class "Default")
      (node (ref "U$1") (pin "P$49") (pinfunction "PD3_P$49") (pintype "bidirectional"))
    )
    (net (code "238") (name "unconnected-(U$1C-PD4-PadP$50)") (class "Default")
      (node (ref "U$1") (pin "P$50") (pinfunction "PD4_P$50") (pintype "bidirectional"))
    )
    (net (code "239") (name "unconnected-(U$1C-PD5-PadP$51)") (class "Default")
      (node (ref "U$1") (pin "P$51") (pinfunction "PD5_P$51") (pintype "bidirectional"))
    )
    (net (code "240") (name "unconnected-(U$1C-PD6-PadP$52)") (class "Default")
      (node (ref "U$1") (pin "P$52") (pinfunction "PD6_P$52") (pintype "bidirectional"))
    )
    (net (code "241") (name "unconnected-(U$1C-PD7-PadP$53)") (class "Default")
      (node (ref "U$1") (pin "P$53") (pinfunction "PD7_P$53") (pintype "bidirectional"))
    )
    (net (code "242") (name "unconnected-(U$1C-PE0-PadP$60)") (class "Default")
      (node (ref "U$1") (pin "P$60") (pinfunction "PE0_P$60") (pintype "bidirectional"))
    )
    (net (code "243") (name "unconnected-(U$1C-PE1-PadP$61)") (class "Default")
      (node (ref "U$1") (pin "P$61") (pinfunction "PE1_P$61") (pintype "bidirectional"))
    )
    (net (code "244") (name "unconnected-(U$1D-PA0-PadP$75)") (class "Default")
      (node (ref "U$1") (pin "P$75") (pinfunction "PA0_P$75") (pintype "bidirectional"))
    )
    (net (code "245") (name "unconnected-(U$1D-PA1-PadP$76)") (class "Default")
      (node (ref "U$1") (pin "P$76") (pinfunction "PA1_P$76") (pintype "bidirectional"))
    )
    (net (code "246") (name "unconnected-(U$1D-PA2-PadP$77)") (class "Default")
      (node (ref "U$1") (pin "P$77") (pinfunction "PA2_P$77") (pintype "bidirectional"))
    )
    (net (code "247") (name "unconnected-(U$1D-PC0-PadP$71)") (class "Default")
      (node (ref "U$1") (pin "P$71") (pinfunction "PC0_P$71") (pintype "bidirectional"))
    )
    (net (code "248") (name "unconnected-(U$1D-PC1-PadP$72)") (class "Default")
      (node (ref "U$1") (pin "P$72") (pinfunction "PC1_P$72") (pintype "bidirectional"))
    )
    (net (code "249") (name "unconnected-(U$1D-PC2-PadP$73)") (class "Default")
      (node (ref "U$1") (pin "P$73") (pinfunction "PC2_P$73") (pintype "bidirectional"))
    )
    (net (code "250") (name "unconnected-(U$1D-PC3-PadP$74)") (class "Default")
      (node (ref "U$1") (pin "P$74") (pinfunction "PC3_P$74") (pintype "bidirectional"))
    )
    (net (code "251") (name "unconnected-(U$1D-PC13-PadP$68)") (class "Default")
      (node (ref "U$1") (pin "P$68") (pinfunction "PC13_P$68") (pintype "bidirectional"))
    )
    (net (code "252") (name "unconnected-(U$1D-PE2-PadP$63)") (class "Default")
      (node (ref "U$1") (pin "P$63") (pinfunction "PE2_P$63") (pintype "bidirectional"))
    )
    (net (code "253") (name "unconnected-(U$1D-PE3-PadP$64)") (class "Default")
      (node (ref "U$1") (pin "P$64") (pinfunction "PE3_P$64") (pintype "bidirectional"))
    )
    (net (code "254") (name "unconnected-(U$1D-PE4-PadP$65)") (class "Default")
      (node (ref "U$1") (pin "P$65") (pinfunction "PE4_P$65") (pintype "bidirectional"))
    )
    (net (code "255") (name "unconnected-(U$1D-PE5-PadP$66)") (class "Default")
      (node (ref "U$1") (pin "P$66") (pinfunction "PE5_P$66") (pintype "bidirectional"))
    )
    (net (code "256") (name "unconnected-(U$1D-PE6-PadP$67)") (class "Default")
      (node (ref "U$1") (pin "P$67") (pinfunction "PE6_P$67") (pintype "bidirectional"))
    )
    (net (code "257") (name "unconnected-(U$30-{slash}OUT15-Pad23)") (class "Default")
      (node (ref "U$30") (pin "23") (pinfunction "/OUT15_23") (pintype "bidirectional"))
    )
    (net (code "258") (name "unconnected-(U$33-{slash}OUT15-Pad23)") (class "Default")
      (node (ref "U$33") (pin "23") (pinfunction "/OUT15_23") (pintype "bidirectional"))
    )
    (net (code "259") (name "unconnected-(U$36-{slash}OUT15-Pad23)") (class "Default")
      (node (ref "U$36") (pin "23") (pinfunction "/OUT15_23") (pintype "bidirectional"))
    )
    (net (code "260") (name "unconnected-(U$51-{slash}OUT15-Pad23)") (class "Default")
      (node (ref "U$51") (pin "23") (pinfunction "/OUT15_23") (pintype "bidirectional"))
    )
  )
)
